# P20_Relay_Board_V1.net
KiCad netlist of a schematic drawn in EAGLE
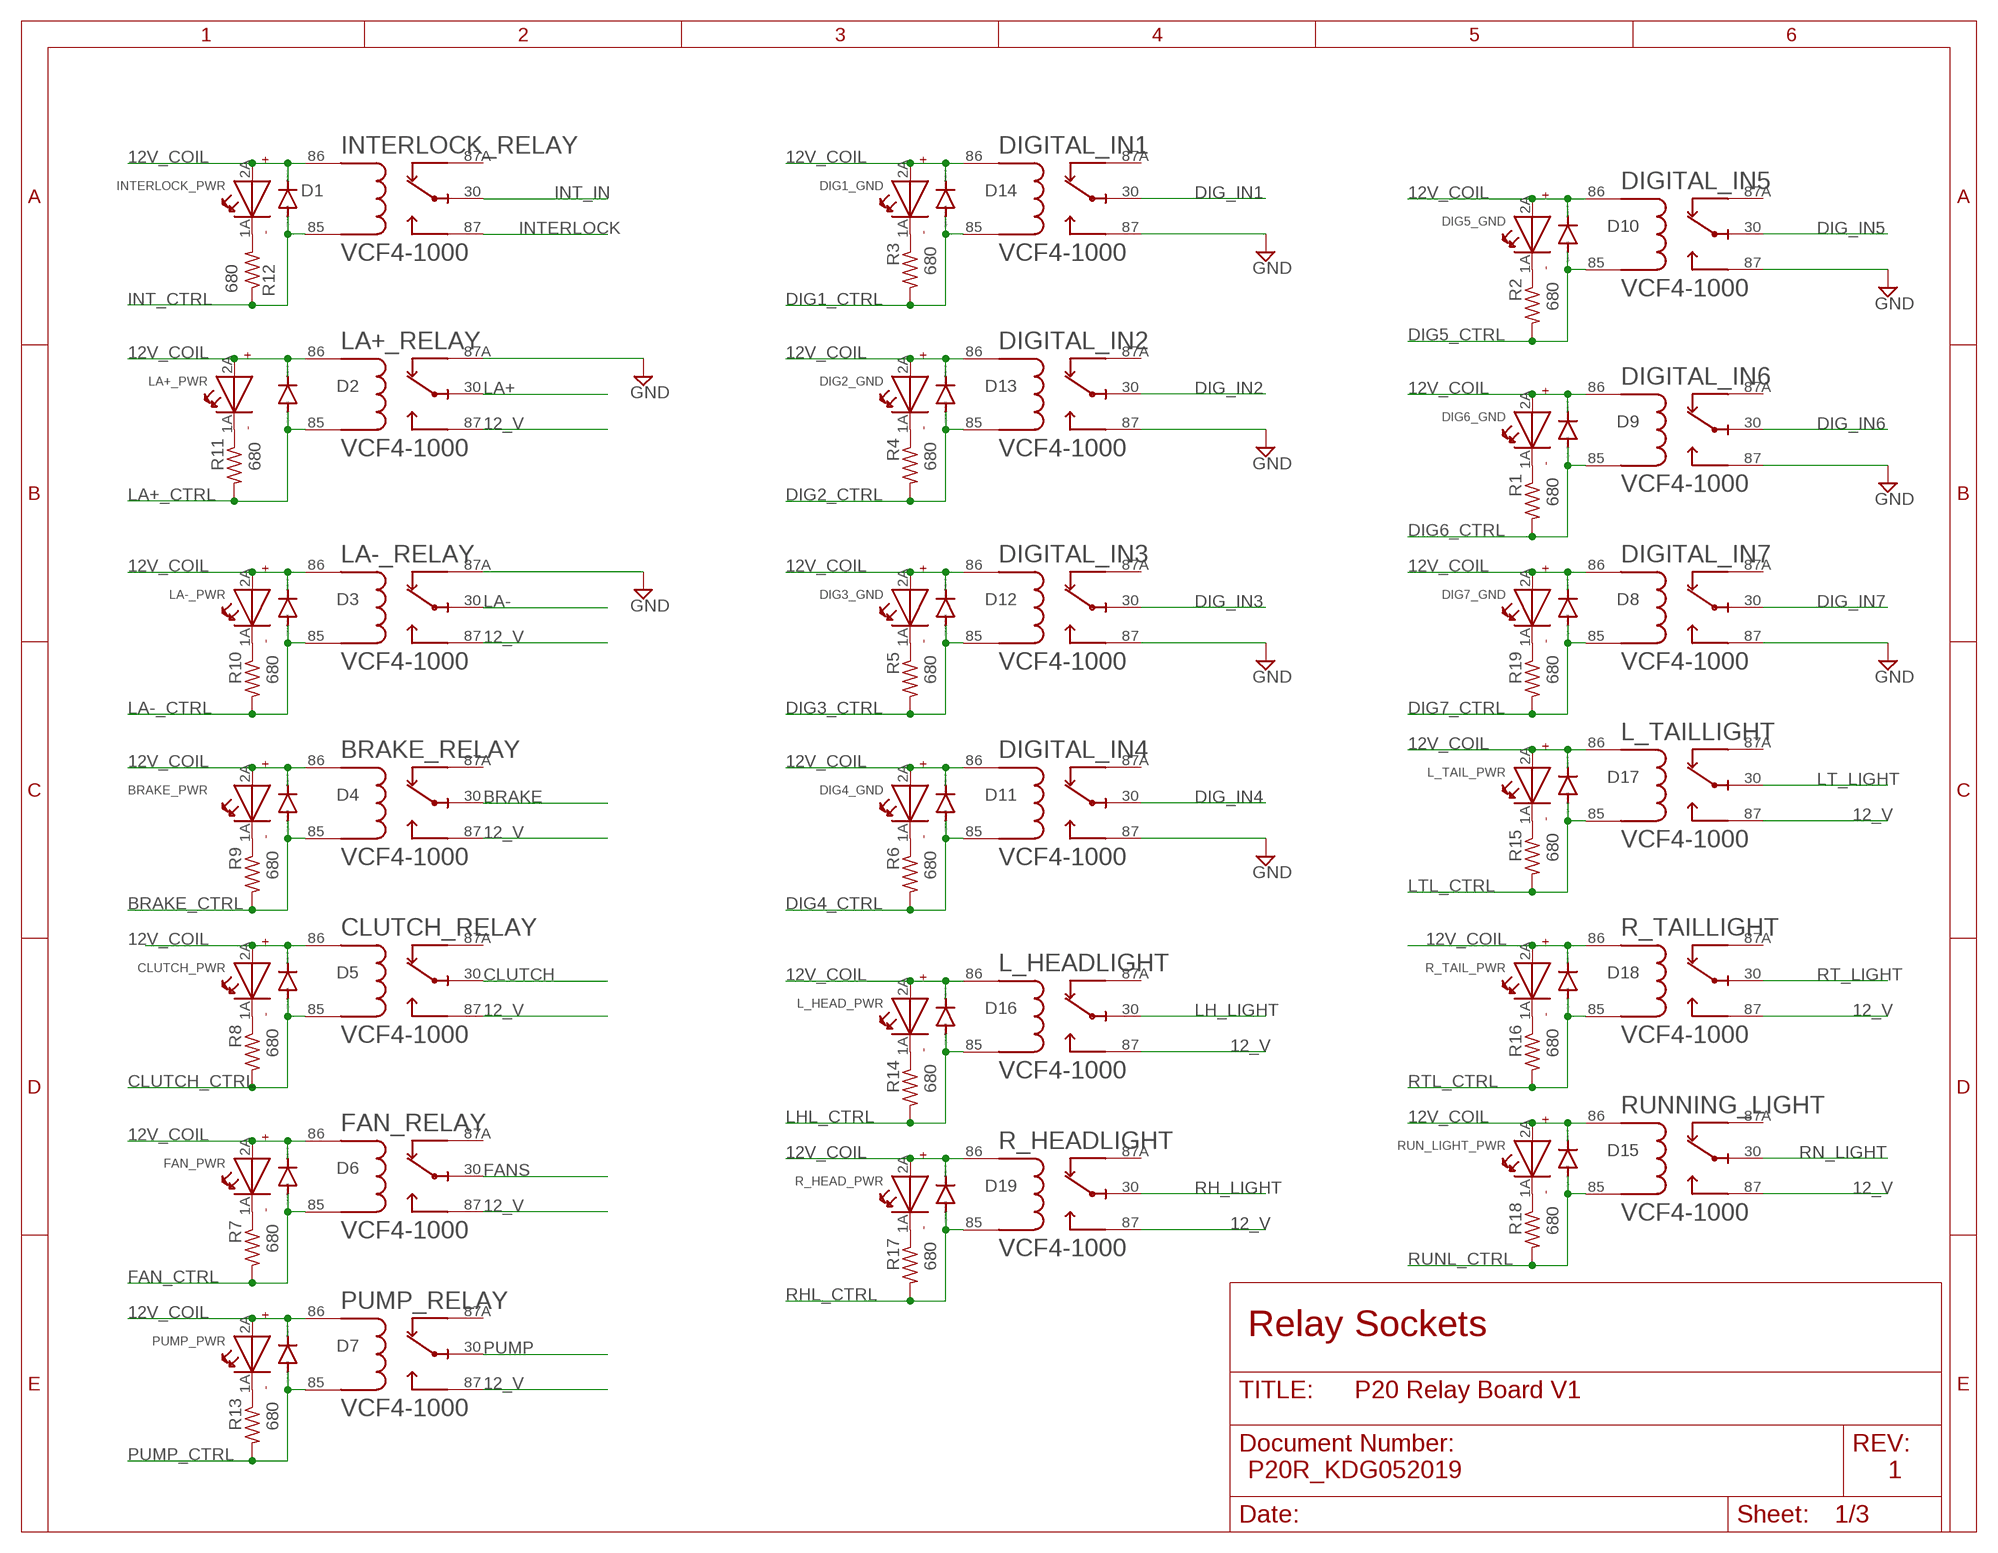
[diagram p0: schematic, sheet 1]
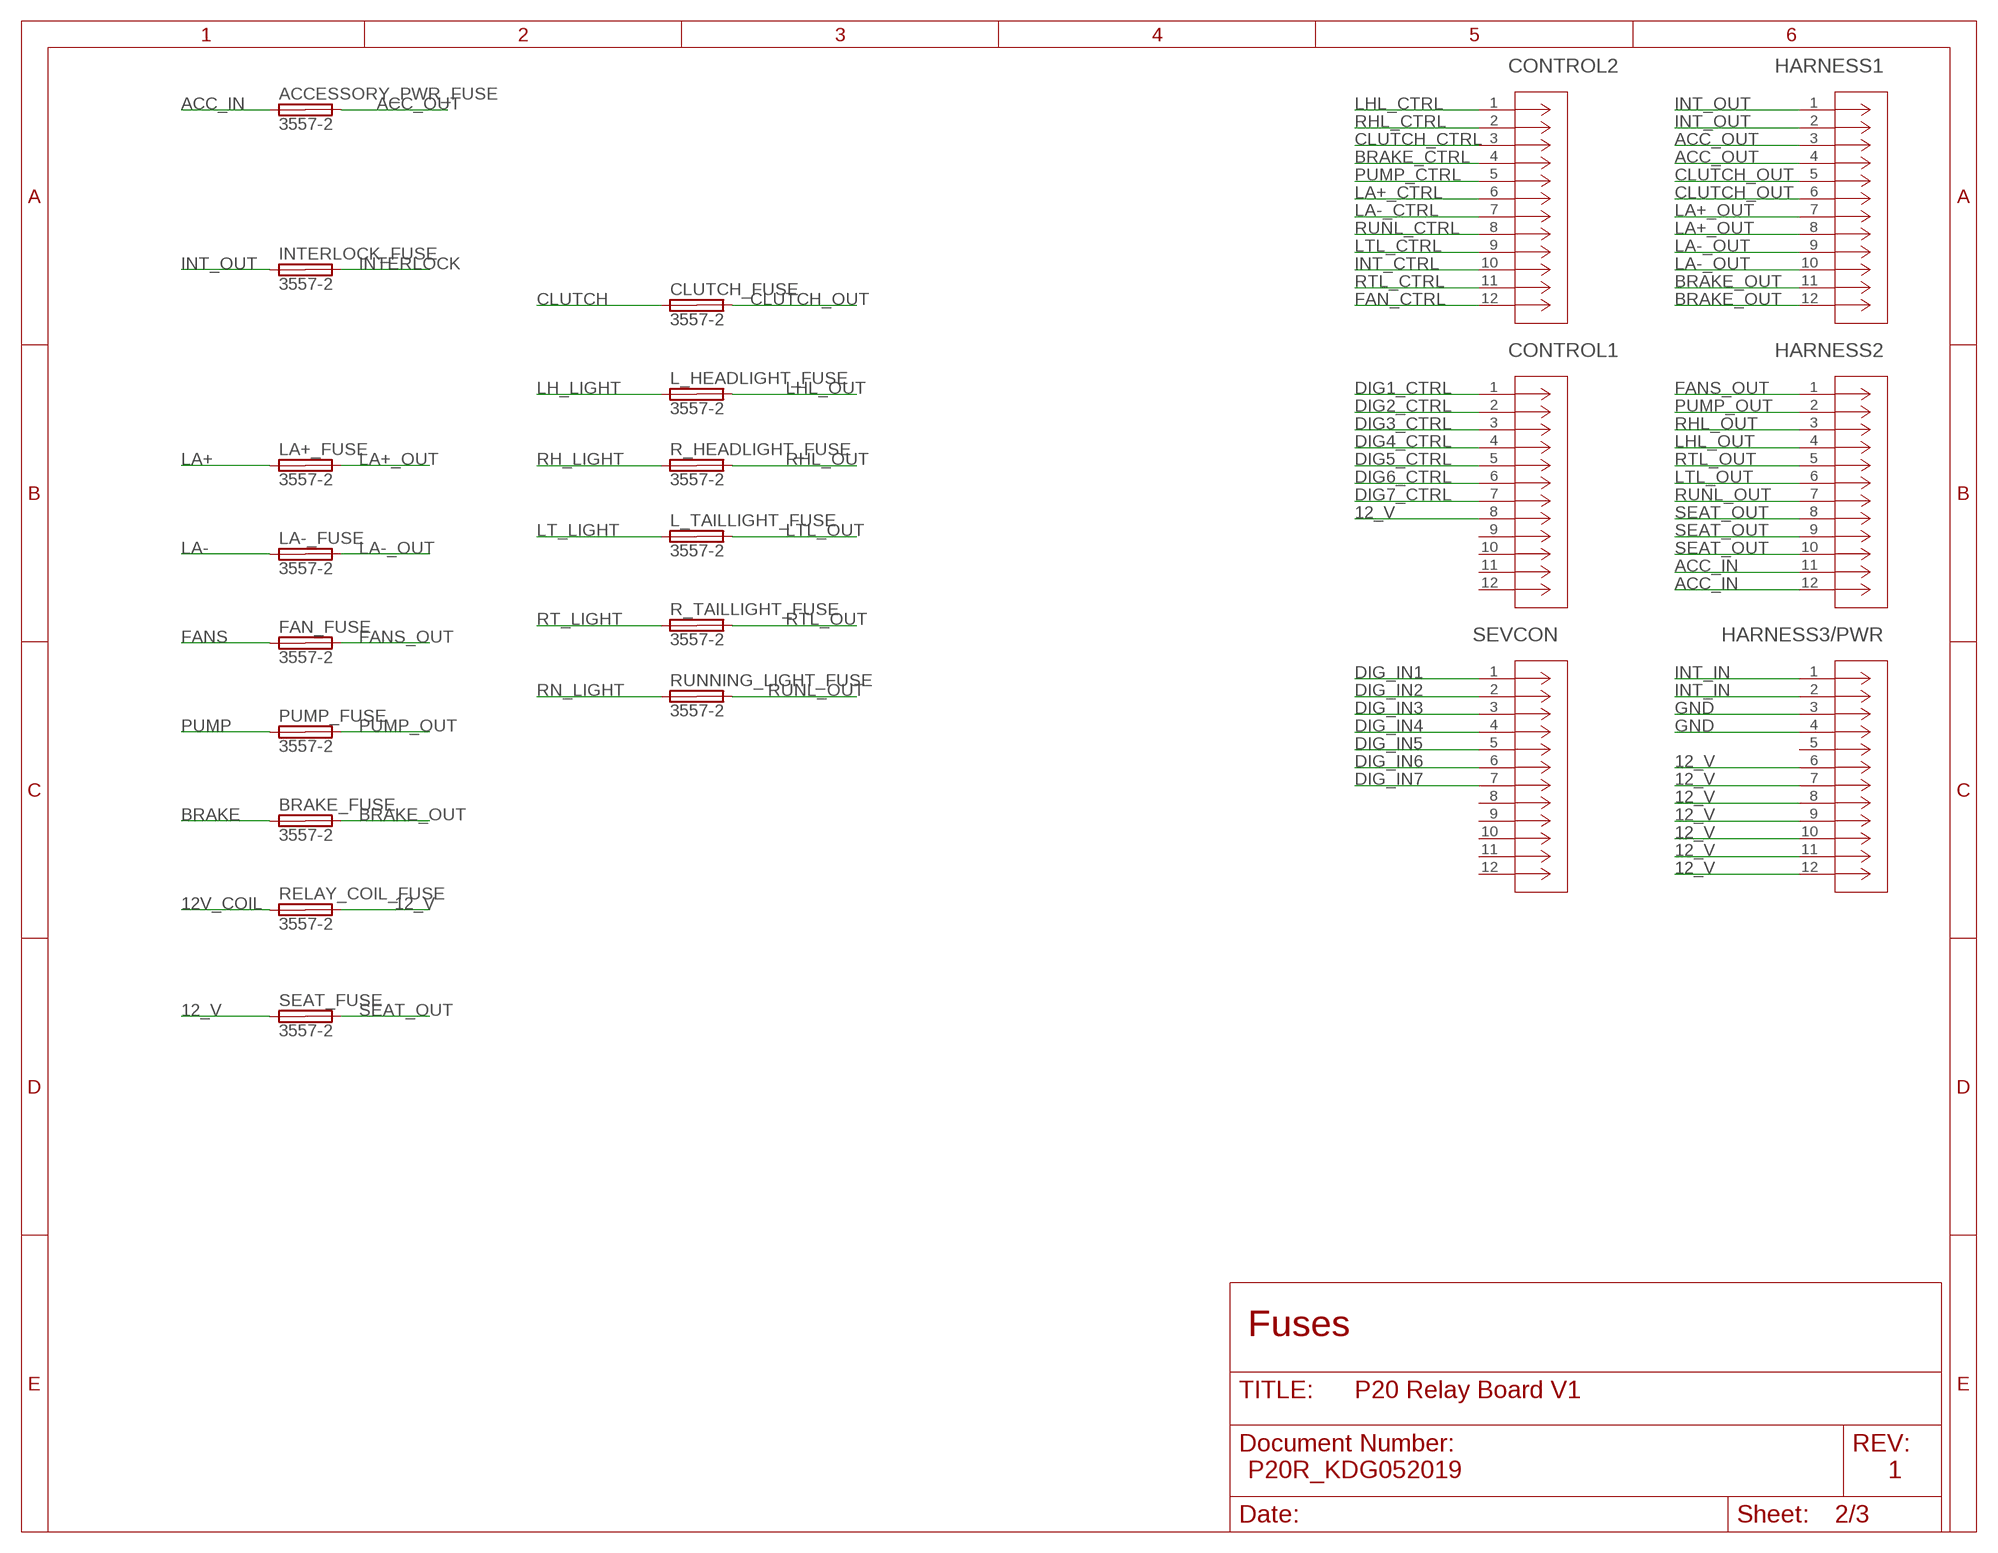
[diagram p1: schematic, sheet 2]
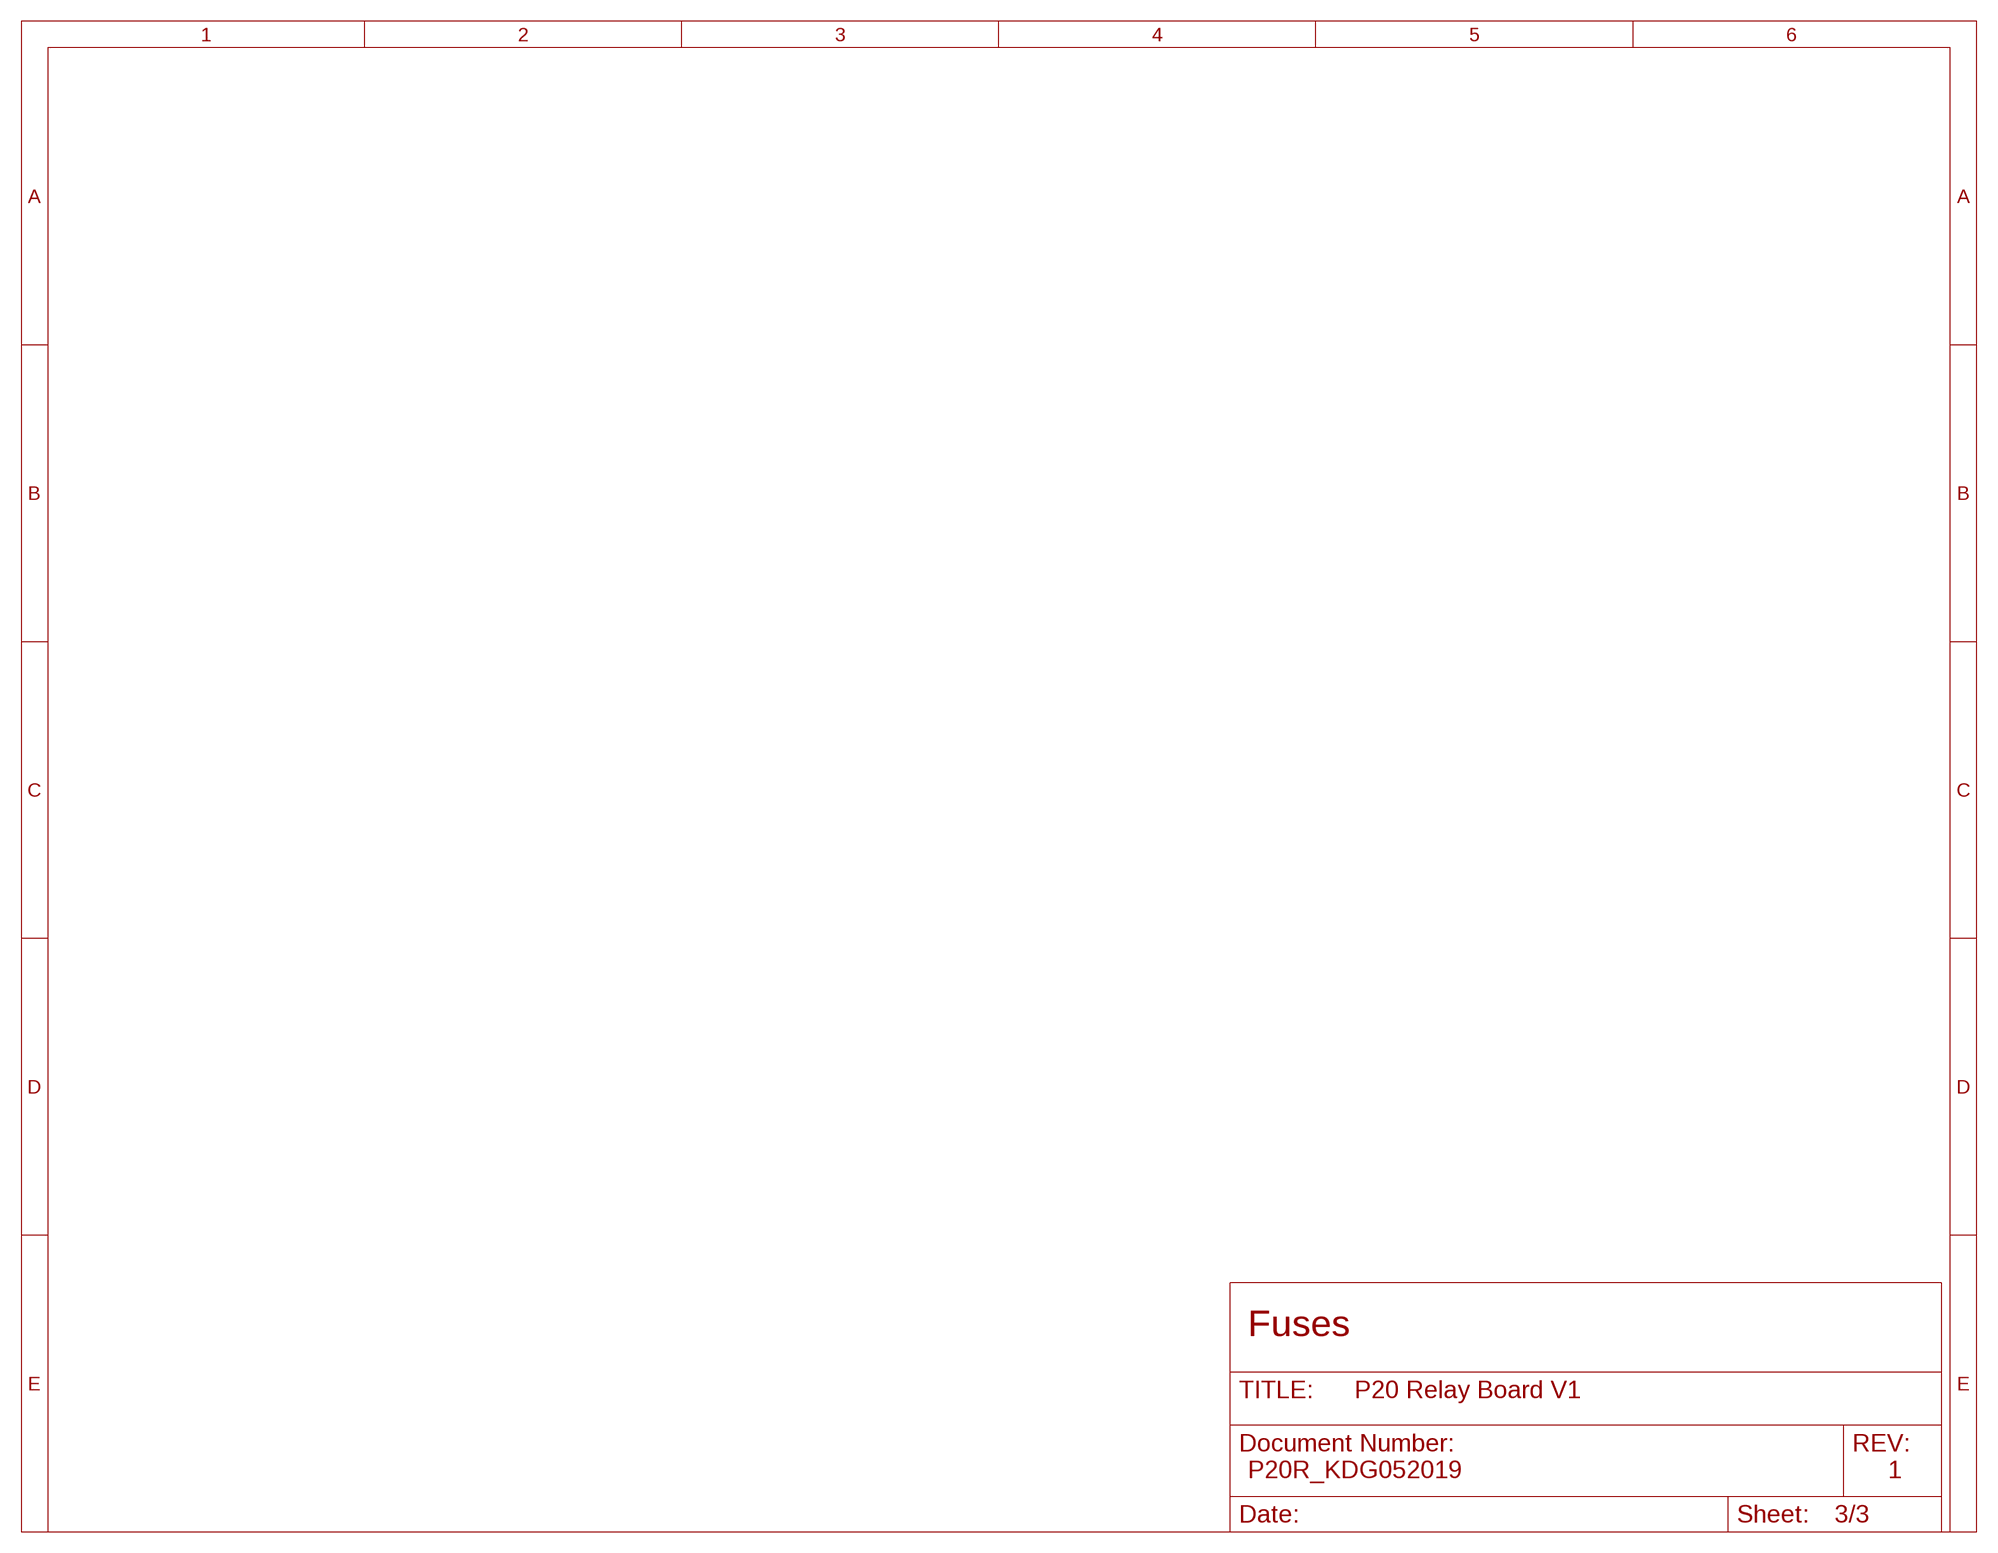
[diagram p2: schematic, sheet 3]

(export (version "E")
  (design (tool "Eeschema 10.0.6"))
  (components
    (comp (ref "ACCESSORY_PWR_FUSE")
      (value "3557-2")
      (footprint "eagle-import:FUSE_3557-2")
      (fields (field (name "MF") "Keystone"))
      (libsource (lib "eagle-import") (part "3557-2"))
    )
    (comp (ref "BRAKE_FUSE")
      (value "3557-2")
      (footprint "eagle-import:FUSE_3557-2")
      (fields (field (name "MF") "Keystone"))
      (libsource (lib "eagle-import") (part "3557-2"))
    )
    (comp (ref "CLUTCH_FUSE")
      (value "3557-2")
      (footprint "eagle-import:FUSE_3557-2")
      (fields (field (name "MF") "Keystone"))
      (libsource (lib "eagle-import") (part "3557-2"))
    )
    (comp (ref "CONTROL1")
      (value "DTM13-12PA")
      (footprint "eagle-import:CONN12_DTM13-12PA")
      (fields (field (name "MANUFACTURER_PART_NUMBER") "DTM1312PA"))
      (libsource (lib "eagle-import") (part "DTM13-12PA"))
    )
    (comp (ref "CONTROL2")
      (value "DTM13-12PA")
      (footprint "eagle-import:CONN12_DTM13-12PA")
      (fields (field (name "MANUFACTURER_PART_NUMBER") "DTM1312PA"))
      (libsource (lib "eagle-import") (part "DTM13-12PA"))
    )
    (comp (ref "FAN_FUSE")
      (value "3557-2")
      (footprint "eagle-import:FUSE_3557-2")
      (fields (field (name "MF") "Keystone"))
      (libsource (lib "eagle-import") (part "3557-2"))
    )
    (comp (ref "HARNESS1")
      (value "DTM13-12PA")
      (footprint "eagle-import:CONN12_DTM13-12PA")
      (fields (field (name "MANUFACTURER_PART_NUMBER") "DTM1312PA"))
      (libsource (lib "eagle-import") (part "DTM13-12PA"))
    )
    (comp (ref "HARNESS2")
      (value "DTM13-12PA")
      (footprint "eagle-import:CONN12_DTM13-12PA")
      (fields (field (name "MANUFACTURER_PART_NUMBER") "DTM1312PA"))
      (libsource (lib "eagle-import") (part "DTM13-12PA"))
    )
    (comp (ref "HARNESS3/PWR")
      (value "DTM13-12PA")
      (footprint "eagle-import:CONN12_DTM13-12PA")
      (fields (field (name "MANUFACTURER_PART_NUMBER") "DTM1312PA"))
      (libsource (lib "eagle-import") (part "DTM13-12PA"))
    )
    (comp (ref "INTERLOCK_FUSE")
      (value "3557-2")
      (footprint "eagle-import:FUSE_3557-2")
      (fields (field (name "MF") "Keystone"))
      (libsource (lib "eagle-import") (part "3557-2"))
    )
    (comp (ref "LA+_FUSE")
      (value "3557-2")
      (footprint "eagle-import:FUSE_3557-2")
      (fields (field (name "MF") "Keystone"))
      (libsource (lib "eagle-import") (part "3557-2"))
    )
    (comp (ref "LA-_FUSE")
      (value "3557-2")
      (footprint "eagle-import:FUSE_3557-2")
      (fields (field (name "MF") "Keystone"))
      (libsource (lib "eagle-import") (part "3557-2"))
    )
    (comp (ref "L_HEADLIGHT_FUSE")
      (value "3557-2")
      (footprint "eagle-import:FUSE_3557-2")
      (fields (field (name "MF") "Keystone"))
      (libsource (lib "eagle-import") (part "3557-2"))
    )
    (comp (ref "L_TAILLIGHT_FUSE")
      (value "3557-2")
      (footprint "eagle-import:FUSE_3557-2")
      (fields (field (name "MF") "Keystone"))
      (libsource (lib "eagle-import") (part "3557-2"))
    )
    (comp (ref "PUMP_FUSE")
      (value "3557-2")
      (footprint "eagle-import:FUSE_3557-2")
      (fields (field (name "MF") "Keystone"))
      (libsource (lib "eagle-import") (part "3557-2"))
    )
    (comp (ref "RELAY_COIL_FUSE")
      (value "3557-2")
      (footprint "eagle-import:FUSE_3557-2")
      (fields (field (name "MF") "Keystone"))
      (libsource (lib "eagle-import") (part "3557-2"))
    )
    (comp (ref "RUNNING_LIGHT_FUSE")
      (value "3557-2")
      (footprint "eagle-import:FUSE_3557-2")
      (fields (field (name "MF") "Keystone"))
      (libsource (lib "eagle-import") (part "3557-2"))
    )
    (comp (ref "R_HEADLIGHT_FUSE")
      (value "3557-2")
      (footprint "eagle-import:FUSE_3557-2")
      (fields (field (name "MF") "Keystone"))
      (libsource (lib "eagle-import") (part "3557-2"))
    )
    (comp (ref "R_TAILLIGHT_FUSE")
      (value "3557-2")
      (footprint "eagle-import:FUSE_3557-2")
      (fields (field (name "MF") "Keystone"))
      (libsource (lib "eagle-import") (part "3557-2"))
    )
    (comp (ref "SEAT_FUSE")
      (value "3557-2")
      (footprint "eagle-import:FUSE_3557-2")
      (fields (field (name "MF") "Keystone"))
      (libsource (lib "eagle-import") (part "3557-2"))
    )
    (comp (ref "SEVCON")
      (value "DTM13-12PA")
      (footprint "eagle-import:CONN12_DTM13-12PA")
      (fields (field (name "MANUFACTURER_PART_NUMBER") "DTM1312PA"))
      (libsource (lib "eagle-import") (part "DTM13-12PA"))
    )
    (comp (ref "BRAKE_PWR")
      (value "WL-TMRW151033BS03000-B")
      (footprint "eagle-import:LED-3MM-ROUND")
      (fields
        (field (name "DIGI-KEY_PART_NUMBER") "732-5013-ND")
        (field (name "MF") "Wurth Electronics")
        (field (name "MP") "151033RS03000")
      )
      (libsource (lib "eagle-import") (part "WL-TMRW151033BS03000-B"))
    )
    (comp (ref "BRAKE_RELAY")
      (value "VCF4-1000")
      (footprint "eagle-import:TE_VCF4-1000")
      (fields
        (field (name "COMMENT") "1393310-3")
        (field (name "DIGI-KEY_PART_NUMBER") "PB232-ND")
        (field (name "MF") "TE Connectivity")
      )
      (libsource (lib "eagle-import") (part "VCF4-1000"))
    )
    (comp (ref "CLUTCH_PWR")
      (value "WL-TMRW151033BS03000-B")
      (footprint "eagle-import:LED-3MM-ROUND")
      (fields
        (field (name "DIGI-KEY_PART_NUMBER") "732-5013-ND")
        (field (name "MF") "Wurth Electronics")
        (field (name "MP") "151033RS03000")
      )
      (libsource (lib "eagle-import") (part "WL-TMRW151033BS03000-B"))
    )
    (comp (ref "CLUTCH_RELAY")
      (value "VCF4-1000")
      (footprint "eagle-import:TE_VCF4-1000")
      (fields
        (field (name "COMMENT") "1393310-3")
        (field (name "DIGI-KEY_PART_NUMBER") "PB232-ND")
        (field (name "MF") "TE Connectivity")
      )
      (libsource (lib "eagle-import") (part "VCF4-1000"))
    )
    (comp (ref "D1")
      (value "1N4004")
      (footprint "eagle-import:DO41-10")
      (libsource (lib "eagle-import") (part "1N4004"))
    )
    (comp (ref "D2")
      (value "1N4004")
      (footprint "eagle-import:DO41-10")
      (libsource (lib "eagle-import") (part "1N4004"))
    )
    (comp (ref "D3")
      (value "1N4004")
      (footprint "eagle-import:DO41-10")
      (libsource (lib "eagle-import") (part "1N4004"))
    )
    (comp (ref "D4")
      (value "1N4004")
      (footprint "eagle-import:DO41-10")
      (libsource (lib "eagle-import") (part "1N4004"))
    )
    (comp (ref "D5")
      (value "1N4004")
      (footprint "eagle-import:DO41-10")
      (libsource (lib "eagle-import") (part "1N4004"))
    )
    (comp (ref "D6")
      (value "1N4004")
      (footprint "eagle-import:DO41-10")
      (libsource (lib "eagle-import") (part "1N4004"))
    )
    (comp (ref "D7")
      (value "1N4004")
      (footprint "eagle-import:DO41-10")
      (libsource (lib "eagle-import") (part "1N4004"))
    )
    (comp (ref "D8")
      (value "1N4004")
      (footprint "eagle-import:DO41-10")
      (libsource (lib "eagle-import") (part "1N4004"))
    )
    (comp (ref "D9")
      (value "1N4004")
      (footprint "eagle-import:DO41-10")
      (libsource (lib "eagle-import") (part "1N4004"))
    )
    (comp (ref "D10")
      (value "1N4004")
      (footprint "eagle-import:DO41-10")
      (libsource (lib "eagle-import") (part "1N4004"))
    )
    (comp (ref "D11")
      (value "1N4004")
      (footprint "eagle-import:DO41-10")
      (libsource (lib "eagle-import") (part "1N4004"))
    )
    (comp (ref "D12")
      (value "1N4004")
      (footprint "eagle-import:DO41-10")
      (libsource (lib "eagle-import") (part "1N4004"))
    )
    (comp (ref "D13")
      (value "1N4004")
      (footprint "eagle-import:DO41-10")
      (libsource (lib "eagle-import") (part "1N4004"))
    )
    (comp (ref "D14")
      (value "1N4004")
      (footprint "eagle-import:DO41-10")
      (libsource (lib "eagle-import") (part "1N4004"))
    )
    (comp (ref "D15")
      (value "1N4004")
      (footprint "eagle-import:DO41-10")
      (libsource (lib "eagle-import") (part "1N4004"))
    )
    (comp (ref "D16")
      (value "1N4004")
      (footprint "eagle-import:DO41-10")
      (libsource (lib "eagle-import") (part "1N4004"))
    )
    (comp (ref "D17")
      (value "1N4004")
      (footprint "eagle-import:DO41-10")
      (libsource (lib "eagle-import") (part "1N4004"))
    )
    (comp (ref "D18")
      (value "1N4004")
      (footprint "eagle-import:DO41-10")
      (libsource (lib "eagle-import") (part "1N4004"))
    )
    (comp (ref "D19")
      (value "1N4004")
      (footprint "eagle-import:DO41-10")
      (libsource (lib "eagle-import") (part "1N4004"))
    )
    (comp (ref "DIG1_GND")
      (value "WL-TMRW151033BS03000-B")
      (footprint "eagle-import:LED-3MM-ROUND")
      (fields
        (field (name "DIGI-KEY_PART_NUMBER") "732-5013-ND")
        (field (name "MF") "Wurth Electronics")
        (field (name "MP") "151033RS03000")
      )
      (libsource (lib "eagle-import") (part "WL-TMRW151033BS03000-B"))
    )
    (comp (ref "DIG2_GND")
      (value "WL-TMRW151033BS03000-B")
      (footprint "eagle-import:LED-3MM-ROUND")
      (fields
        (field (name "DIGI-KEY_PART_NUMBER") "732-5013-ND")
        (field (name "MF") "Wurth Electronics")
        (field (name "MP") "151033RS03000")
      )
      (libsource (lib "eagle-import") (part "WL-TMRW151033BS03000-B"))
    )
    (comp (ref "DIG3_GND")
      (value "WL-TMRW151033BS03000-B")
      (footprint "eagle-import:LED-3MM-ROUND")
      (fields
        (field (name "DIGI-KEY_PART_NUMBER") "732-5013-ND")
        (field (name "MF") "Wurth Electronics")
        (field (name "MP") "151033RS03000")
      )
      (libsource (lib "eagle-import") (part "WL-TMRW151033BS03000-B"))
    )
    (comp (ref "DIG4_GND")
      (value "WL-TMRW151033BS03000-B")
      (footprint "eagle-import:LED-3MM-ROUND")
      (fields
        (field (name "DIGI-KEY_PART_NUMBER") "732-5013-ND")
        (field (name "MF") "Wurth Electronics")
        (field (name "MP") "151033RS03000")
      )
      (libsource (lib "eagle-import") (part "WL-TMRW151033BS03000-B"))
    )
    (comp (ref "DIG5_GND")
      (value "WL-TMRW151033BS03000-B")
      (footprint "eagle-import:LED-3MM-ROUND")
      (fields
        (field (name "DIGI-KEY_PART_NUMBER") "732-5013-ND")
        (field (name "MF") "Wurth Electronics")
        (field (name "MP") "151033RS03000")
      )
      (libsource (lib "eagle-import") (part "WL-TMRW151033BS03000-B"))
    )
    (comp (ref "DIG6_GND")
      (value "WL-TMRW151033BS03000-B")
      (footprint "eagle-import:LED-3MM-ROUND")
      (fields
        (field (name "DIGI-KEY_PART_NUMBER") "732-5013-ND")
        (field (name "MF") "Wurth Electronics")
        (field (name "MP") "151033RS03000")
      )
      (libsource (lib "eagle-import") (part "WL-TMRW151033BS03000-B"))
    )
    (comp (ref "DIG7_GND")
      (value "WL-TMRW151033BS03000-B")
      (footprint "eagle-import:LED-3MM-ROUND")
      (fields
        (field (name "DIGI-KEY_PART_NUMBER") "732-5013-ND")
        (field (name "MF") "Wurth Electronics")
        (field (name "MP") "151033RS03000")
      )
      (libsource (lib "eagle-import") (part "WL-TMRW151033BS03000-B"))
    )
    (comp (ref "DIGITAL_IN1")
      (value "VCF4-1000")
      (footprint "eagle-import:TE_VCF4-1000")
      (fields
        (field (name "COMMENT") "1393310-3")
        (field (name "DIGI-KEY_PART_NUMBER") "PB232-ND")
        (field (name "MF") "TE Connectivity")
      )
      (libsource (lib "eagle-import") (part "VCF4-1000"))
    )
    (comp (ref "DIGITAL_IN2")
      (value "VCF4-1000")
      (footprint "eagle-import:TE_VCF4-1000")
      (fields
        (field (name "COMMENT") "1393310-3")
        (field (name "DIGI-KEY_PART_NUMBER") "PB232-ND")
        (field (name "MF") "TE Connectivity")
      )
      (libsource (lib "eagle-import") (part "VCF4-1000"))
    )
    (comp (ref "DIGITAL_IN3")
      (value "VCF4-1000")
      (footprint "eagle-import:TE_VCF4-1000")
      (fields
        (field (name "COMMENT") "1393310-3")
        (field (name "DIGI-KEY_PART_NUMBER") "PB232-ND")
        (field (name "MF") "TE Connectivity")
      )
      (libsource (lib "eagle-import") (part "VCF4-1000"))
    )
    (comp (ref "DIGITAL_IN4")
      (value "VCF4-1000")
      (footprint "eagle-import:TE_VCF4-1000")
      (fields
        (field (name "COMMENT") "1393310-3")
        (field (name "DIGI-KEY_PART_NUMBER") "PB232-ND")
        (field (name "MF") "TE Connectivity")
      )
      (libsource (lib "eagle-import") (part "VCF4-1000"))
    )
    (comp (ref "DIGITAL_IN5")
      (value "VCF4-1000")
      (footprint "eagle-import:TE_VCF4-1000")
      (fields
        (field (name "COMMENT") "1393310-3")
        (field (name "DIGI-KEY_PART_NUMBER") "PB232-ND")
        (field (name "MF") "TE Connectivity")
      )
      (libsource (lib "eagle-import") (part "VCF4-1000"))
    )
    (comp (ref "DIGITAL_IN6")
      (value "VCF4-1000")
      (footprint "eagle-import:TE_VCF4-1000")
      (fields
        (field (name "COMMENT") "1393310-3")
        (field (name "DIGI-KEY_PART_NUMBER") "PB232-ND")
        (field (name "MF") "TE Connectivity")
      )
      (libsource (lib "eagle-import") (part "VCF4-1000"))
    )
    (comp (ref "DIGITAL_IN7")
      (value "VCF4-1000")
      (footprint "eagle-import:TE_VCF4-1000")
      (fields
        (field (name "COMMENT") "1393310-3")
        (field (name "DIGI-KEY_PART_NUMBER") "PB232-ND")
        (field (name "MF") "TE Connectivity")
      )
      (libsource (lib "eagle-import") (part "VCF4-1000"))
    )
    (comp (ref "FAN_PWR")
      (value "WL-TMRW151033BS03000-B")
      (footprint "eagle-import:LED-3MM-ROUND")
      (fields
        (field (name "DIGI-KEY_PART_NUMBER") "732-5013-ND")
        (field (name "MF") "Wurth Electronics")
        (field (name "MP") "151033RS03000")
      )
      (libsource (lib "eagle-import") (part "WL-TMRW151033BS03000-B"))
    )
    (comp (ref "FAN_RELAY")
      (value "VCF4-1000")
      (footprint "eagle-import:TE_VCF4-1000")
      (fields
        (field (name "COMMENT") "1393310-3")
        (field (name "DIGI-KEY_PART_NUMBER") "PB232-ND")
        (field (name "MF") "TE Connectivity")
      )
      (libsource (lib "eagle-import") (part "VCF4-1000"))
    )
    (comp (ref "INTERLOCK_PWR")
      (value "WL-TMRW151033BS03000-B")
      (footprint "eagle-import:LED-3MM-ROUND")
      (fields
        (field (name "DIGI-KEY_PART_NUMBER") "732-5013-ND")
        (field (name "MF") "Wurth Electronics")
        (field (name "MP") "151033RS03000")
      )
      (libsource (lib "eagle-import") (part "WL-TMRW151033BS03000-B"))
    )
    (comp (ref "INTERLOCK_RELAY")
      (value "VCF4-1000")
      (footprint "eagle-import:TE_VCF4-1000")
      (fields
        (field (name "COMMENT") "1393310-3")
        (field (name "DIGI-KEY_PART_NUMBER") "PB232-ND")
        (field (name "MF") "TE Connectivity")
      )
      (libsource (lib "eagle-import") (part "VCF4-1000"))
    )
    (comp (ref "LA+_PWR")
      (value "WL-TMRW151033BS03000-B")
      (footprint "eagle-import:LED-3MM-ROUND")
      (fields
        (field (name "DIGI-KEY_PART_NUMBER") "732-5013-ND")
        (field (name "MF") "Wurth Electronics")
        (field (name "MP") "151033RS03000")
      )
      (libsource (lib "eagle-import") (part "WL-TMRW151033BS03000-B"))
    )
    (comp (ref "LA+_RELAY")
      (value "VCF4-1000")
      (footprint "eagle-import:TE_VCF4-1000")
      (fields
        (field (name "COMMENT") "1393310-3")
        (field (name "DIGI-KEY_PART_NUMBER") "PB232-ND")
        (field (name "MF") "TE Connectivity")
      )
      (libsource (lib "eagle-import") (part "VCF4-1000"))
    )
    (comp (ref "LA-_PWR")
      (value "WL-TMRW151033BS03000-B")
      (footprint "eagle-import:LED-3MM-ROUND")
      (fields
        (field (name "DIGI-KEY_PART_NUMBER") "732-5013-ND")
        (field (name "MF") "Wurth Electronics")
        (field (name "MP") "151033RS03000")
      )
      (libsource (lib "eagle-import") (part "WL-TMRW151033BS03000-B"))
    )
    (comp (ref "LA-_RELAY")
      (value "VCF4-1000")
      (footprint "eagle-import:TE_VCF4-1000")
      (fields
        (field (name "COMMENT") "1393310-3")
        (field (name "DIGI-KEY_PART_NUMBER") "PB232-ND")
        (field (name "MF") "TE Connectivity")
      )
      (libsource (lib "eagle-import") (part "VCF4-1000"))
    )
    (comp (ref "L_HEADLIGHT")
      (value "VCF4-1000")
      (footprint "eagle-import:TE_VCF4-1000")
      (fields
        (field (name "COMMENT") "1393310-3")
        (field (name "DIGI-KEY_PART_NUMBER") "PB232-ND")
        (field (name "MF") "TE Connectivity")
      )
      (libsource (lib "eagle-import") (part "VCF4-1000"))
    )
    (comp (ref "L_HEAD_PWR")
      (value "WL-TMRW151033BS03000-B")
      (footprint "eagle-import:LED-3MM-ROUND")
      (fields
        (field (name "DIGI-KEY_PART_NUMBER") "732-5013-ND")
        (field (name "MF") "Wurth Electronics")
        (field (name "MP") "151033RS03000")
      )
      (libsource (lib "eagle-import") (part "WL-TMRW151033BS03000-B"))
    )
    (comp (ref "L_TAILLIGHT")
      (value "VCF4-1000")
      (footprint "eagle-import:TE_VCF4-1000")
      (fields
        (field (name "COMMENT") "1393310-3")
        (field (name "DIGI-KEY_PART_NUMBER") "PB232-ND")
        (field (name "MF") "TE Connectivity")
      )
      (libsource (lib "eagle-import") (part "VCF4-1000"))
    )
    (comp (ref "L_TAIL_PWR")
      (value "WL-TMRW151033BS03000-B")
      (footprint "eagle-import:LED-3MM-ROUND")
      (fields
        (field (name "DIGI-KEY_PART_NUMBER") "732-5013-ND")
        (field (name "MF") "Wurth Electronics")
        (field (name "MP") "151033RS03000")
      )
      (libsource (lib "eagle-import") (part "WL-TMRW151033BS03000-B"))
    )
    (comp (ref "PUMP_PWR")
      (value "WL-TMRW151033BS03000-B")
      (footprint "eagle-import:LED-3MM-ROUND")
      (fields
        (field (name "DIGI-KEY_PART_NUMBER") "732-5013-ND")
        (field (name "MF") "Wurth Electronics")
        (field (name "MP") "151033RS03000")
      )
      (libsource (lib "eagle-import") (part "WL-TMRW151033BS03000-B"))
    )
    (comp (ref "PUMP_RELAY")
      (value "VCF4-1000")
      (footprint "eagle-import:TE_VCF4-1000")
      (fields
        (field (name "COMMENT") "1393310-3")
        (field (name "DIGI-KEY_PART_NUMBER") "PB232-ND")
        (field (name "MF") "TE Connectivity")
      )
      (libsource (lib "eagle-import") (part "VCF4-1000"))
    )
    (comp (ref "R1")
      (value "680")
      (footprint "eagle-import:0207_10")
      (libsource (lib "eagle-import") (part "R-US_0207/10"))
    )
    (comp (ref "R2")
      (value "680")
      (footprint "eagle-import:0207_10")
      (libsource (lib "eagle-import") (part "R-US_0207/10"))
    )
    (comp (ref "R3")
      (value "680")
      (footprint "eagle-import:0207_10")
      (libsource (lib "eagle-import") (part "R-US_0207/10"))
    )
    (comp (ref "R4")
      (value "680")
      (footprint "eagle-import:0207_10")
      (libsource (lib "eagle-import") (part "R-US_0207/10"))
    )
    (comp (ref "R5")
      (value "680")
      (footprint "eagle-import:0207_10")
      (libsource (lib "eagle-import") (part "R-US_0207/10"))
    )
    (comp (ref "R6")
      (value "680")
      (footprint "eagle-import:0207_10")
      (libsource (lib "eagle-import") (part "R-US_0207/10"))
    )
    (comp (ref "R7")
      (value "680")
      (footprint "eagle-import:0207_10")
      (libsource (lib "eagle-import") (part "R-US_0207/10"))
    )
    (comp (ref "R8")
      (value "680")
      (footprint "eagle-import:0207_10")
      (libsource (lib "eagle-import") (part "R-US_0207/10"))
    )
    (comp (ref "R9")
      (value "680")
      (footprint "eagle-import:0207_10")
      (libsource (lib "eagle-import") (part "R-US_0207/10"))
    )
    (comp (ref "R10")
      (value "680")
      (footprint "eagle-import:0207_10")
      (libsource (lib "eagle-import") (part "R-US_0207/10"))
    )
    (comp (ref "R11")
      (value "680")
      (footprint "eagle-import:0207_10")
      (libsource (lib "eagle-import") (part "R-US_0207/10"))
    )
    (comp (ref "R12")
      (value "680")
      (footprint "eagle-import:0207_10")
      (libsource (lib "eagle-import") (part "R-US_0207/10"))
    )
    (comp (ref "R13")
      (value "680")
      (footprint "eagle-import:0207_10")
      (libsource (lib "eagle-import") (part "R-US_0207/10"))
    )
    (comp (ref "R14")
      (value "680")
      (footprint "eagle-import:0207_10")
      (libsource (lib "eagle-import") (part "R-US_0207/10"))
    )
    (comp (ref "R15")
      (value "680")
      (footprint "eagle-import:0207_10")
      (libsource (lib "eagle-import") (part "R-US_0207/10"))
    )
    (comp (ref "R16")
      (value "680")
      (footprint "eagle-import:0207_10")
      (libsource (lib "eagle-import") (part "R-US_0207/10"))
    )
    (comp (ref "R17")
      (value "680")
      (footprint "eagle-import:0207_10")
      (libsource (lib "eagle-import") (part "R-US_0207/10"))
    )
    (comp (ref "R18")
      (value "680")
      (footprint "eagle-import:0207_10")
      (libsource (lib "eagle-import") (part "R-US_0207/10"))
    )
    (comp (ref "R19")
      (value "680")
      (footprint "eagle-import:0207_10")
      (libsource (lib "eagle-import") (part "R-US_0207/10"))
    )
    (comp (ref "RUNNING_LIGHT")
      (value "VCF4-1000")
      (footprint "eagle-import:TE_VCF4-1000")
      (fields
        (field (name "COMMENT") "1393310-3")
        (field (name "DIGI-KEY_PART_NUMBER") "PB232-ND")
        (field (name "MF") "TE Connectivity")
      )
      (libsource (lib "eagle-import") (part "VCF4-1000"))
    )
    (comp (ref "RUN_LIGHT_PWR")
      (value "WL-TMRW151033BS03000-B")
      (footprint "eagle-import:LED-3MM-ROUND")
      (fields
        (field (name "DIGI-KEY_PART_NUMBER") "732-5013-ND")
        (field (name "MF") "Wurth Electronics")
        (field (name "MP") "151033RS03000")
      )
      (libsource (lib "eagle-import") (part "WL-TMRW151033BS03000-B"))
    )
    (comp (ref "R_HEADLIGHT")
      (value "VCF4-1000")
      (footprint "eagle-import:TE_VCF4-1000")
      (fields
        (field (name "COMMENT") "1393310-3")
        (field (name "DIGI-KEY_PART_NUMBER") "PB232-ND")
        (field (name "MF") "TE Connectivity")
      )
      (libsource (lib "eagle-import") (part "VCF4-1000"))
    )
    (comp (ref "R_HEAD_PWR")
      (value "WL-TMRW151033BS03000-B")
      (footprint "eagle-import:LED-3MM-ROUND")
      (fields
        (field (name "DIGI-KEY_PART_NUMBER") "732-5013-ND")
        (field (name "MF") "Wurth Electronics")
        (field (name "MP") "151033RS03000")
      )
      (libsource (lib "eagle-import") (part "WL-TMRW151033BS03000-B"))
    )
    (comp (ref "R_TAILLIGHT")
      (value "VCF4-1000")
      (footprint "eagle-import:TE_VCF4-1000")
      (fields
        (field (name "COMMENT") "1393310-3")
        (field (name "DIGI-KEY_PART_NUMBER") "PB232-ND")
        (field (name "MF") "TE Connectivity")
      )
      (libsource (lib "eagle-import") (part "VCF4-1000"))
    )
    (comp (ref "R_TAIL_PWR")
      (value "WL-TMRW151033BS03000-B")
      (footprint "eagle-import:LED-3MM-ROUND")
      (fields
        (field (name "DIGI-KEY_PART_NUMBER") "732-5013-ND")
        (field (name "MF") "Wurth Electronics")
        (field (name "MP") "151033RS03000")
      )
      (libsource (lib "eagle-import") (part "WL-TMRW151033BS03000-B"))
    )
  )
  (nets
    (net (code "1") (name "12V_COIL") (class "Default")
      (node (ref "BRAKE_PWR") (pin "2A") (pinfunction "+_2A") (pintype "bidirectional"))
      (node (ref "BRAKE_RELAY") (pin "86") (pinfunction "86_86") (pintype "passive"))
      (node (ref "CLUTCH_PWR") (pin "2A") (pinfunction "+_2A") (pintype "bidirectional"))
      (node (ref "CLUTCH_RELAY") (pin "86") (pinfunction "86_86") (pintype "passive"))
      (node (ref "D1") (pin "C") (pinfunction "C_C") (pintype "passive"))
      (node (ref "D10") (pin "C") (pinfunction "C_C") (pintype "passive"))
      (node (ref "D11") (pin "C") (pinfunction "C_C") (pintype "passive"))
      (node (ref "D12") (pin "C") (pinfunction "C_C") (pintype "passive"))
      (node (ref "D13") (pin "C") (pinfunction "C_C") (pintype "passive"))
      (node (ref "D14") (pin "C") (pinfunction "C_C") (pintype "passive"))
      (node (ref "D15") (pin "C") (pinfunction "C_C") (pintype "passive"))
      (node (ref "D16") (pin "C") (pinfunction "C_C") (pintype "passive"))
      (node (ref "D17") (pin "C") (pinfunction "C_C") (pintype "passive"))
      (node (ref "D18") (pin "C") (pinfunction "C_C") (pintype "passive"))
      (node (ref "D19") (pin "C") (pinfunction "C_C") (pintype "passive"))
      (node (ref "D2") (pin "C") (pinfunction "C_C") (pintype "passive"))
      (node (ref "D3") (pin "C") (pinfunction "C_C") (pintype "passive"))
      (node (ref "D4") (pin "C") (pinfunction "C_C") (pintype "passive"))
      (node (ref "D5") (pin "C") (pinfunction "C_C") (pintype "passive"))
      (node (ref "D6") (pin "C") (pinfunction "C_C") (pintype "passive"))
      (node (ref "D7") (pin "C") (pinfunction "C_C") (pintype "passive"))
      (node (ref "D8") (pin "C") (pinfunction "C_C") (pintype "passive"))
      (node (ref "D9") (pin "C") (pinfunction "C_C") (pintype "passive"))
      (node (ref "DIG1_GND") (pin "2A") (pinfunction "+_2A") (pintype "bidirectional"))
      (node (ref "DIG2_GND") (pin "2A") (pinfunction "+_2A") (pintype "bidirectional"))
      (node (ref "DIG3_GND") (pin "2A") (pinfunction "+_2A") (pintype "bidirectional"))
      (node (ref "DIG4_GND") (pin "2A") (pinfunction "+_2A") (pintype "bidirectional"))
      (node (ref "DIG5_GND") (pin "2A") (pinfunction "+_2A") (pintype "bidirectional"))
      (node (ref "DIG6_GND") (pin "2A") (pinfunction "+_2A") (pintype "bidirectional"))
      (node (ref "DIG7_GND") (pin "2A") (pinfunction "+_2A") (pintype "bidirectional"))
      (node (ref "DIGITAL_IN1") (pin "86") (pinfunction "86_86") (pintype "passive"))
      (node (ref "DIGITAL_IN2") (pin "86") (pinfunction "86_86") (pintype "passive"))
      (node (ref "DIGITAL_IN3") (pin "86") (pinfunction "86_86") (pintype "passive"))
      (node (ref "DIGITAL_IN4") (pin "86") (pinfunction "86_86") (pintype "passive"))
      (node (ref "DIGITAL_IN5") (pin "86") (pinfunction "86_86") (pintype "passive"))
      (node (ref "DIGITAL_IN6") (pin "86") (pinfunction "86_86") (pintype "passive"))
      (node (ref "DIGITAL_IN7") (pin "86") (pinfunction "86_86") (pintype "passive"))
      (node (ref "FAN_PWR") (pin "2A") (pinfunction "+_2A") (pintype "bidirectional"))
      (node (ref "FAN_RELAY") (pin "86") (pinfunction "86_86") (pintype "passive"))
      (node (ref "INTERLOCK_PWR") (pin "2A") (pinfunction "+_2A") (pintype "bidirectional"))
      (node (ref "INTERLOCK_RELAY") (pin "86") (pinfunction "86_86") (pintype "passive"))
      (node (ref "LA+_PWR") (pin "2A") (pinfunction "+_2A") (pintype "bidirectional"))
      (node (ref "LA+_RELAY") (pin "86") (pinfunction "86_86") (pintype "passive"))
      (node (ref "LA-_PWR") (pin "2A") (pinfunction "+_2A") (pintype "bidirectional"))
      (node (ref "LA-_RELAY") (pin "86") (pinfunction "86_86") (pintype "passive"))
      (node (ref "L_HEADLIGHT") (pin "86") (pinfunction "86_86") (pintype "passive"))
      (node (ref "L_HEAD_PWR") (pin "2A") (pinfunction "+_2A") (pintype "bidirectional"))
      (node (ref "L_TAILLIGHT") (pin "86") (pinfunction "86_86") (pintype "passive"))
      (node (ref "L_TAIL_PWR") (pin "2A") (pinfunction "+_2A") (pintype "bidirectional"))
      (node (ref "PUMP_PWR") (pin "2A") (pinfunction "+_2A") (pintype "bidirectional"))
      (node (ref "PUMP_RELAY") (pin "86") (pinfunction "86_86") (pintype "passive"))
      (node (ref "RELAY_COIL_FUSE") (pin "1") (pinfunction "1A_1") (pintype "passive"))
      (node (ref "RUNNING_LIGHT") (pin "86") (pinfunction "86_86") (pintype "passive"))
      (node (ref "RUN_LIGHT_PWR") (pin "2A") (pinfunction "+_2A") (pintype "bidirectional"))
      (node (ref "R_HEADLIGHT") (pin "86") (pinfunction "86_86") (pintype "passive"))
      (node (ref "R_HEAD_PWR") (pin "2A") (pinfunction "+_2A") (pintype "bidirectional"))
      (node (ref "R_TAILLIGHT") (pin "86") (pinfunction "86_86") (pintype "passive"))
      (node (ref "R_TAIL_PWR") (pin "2A") (pinfunction "+_2A") (pintype "bidirectional"))
    )
    (net (code "2") (name "12_V") (class "Default")
      (node (ref "BRAKE_RELAY") (pin "87") (pinfunction "87_87") (pintype "passive"))
      (node (ref "CLUTCH_RELAY") (pin "87") (pinfunction "87_87") (pintype "passive"))
      (node (ref "CONTROL1") (pin "8") (pinfunction "8_8") (pintype "passive"))
      (node (ref "FAN_RELAY") (pin "87") (pinfunction "87_87") (pintype "passive"))
      (node (ref "HARNESS3/PWR") (pin "10") (pinfunction "10_10") (pintype "passive"))
      (node (ref "HARNESS3/PWR") (pin "11") (pinfunction "11_11") (pintype "passive"))
      (node (ref "HARNESS3/PWR") (pin "12") (pinfunction "12_12") (pintype "passive"))
      (node (ref "HARNESS3/PWR") (pin "6") (pinfunction "6_6") (pintype "passive"))
      (node (ref "HARNESS3/PWR") (pin "7") (pinfunction "7_7") (pintype "passive"))
      (node (ref "HARNESS3/PWR") (pin "8") (pinfunction "8_8") (pintype "passive"))
      (node (ref "HARNESS3/PWR") (pin "9") (pinfunction "9_9") (pintype "passive"))
      (node (ref "LA+_RELAY") (pin "87") (pinfunction "87_87") (pintype "passive"))
      (node (ref "LA-_RELAY") (pin "87") (pinfunction "87_87") (pintype "passive"))
      (node (ref "L_HEADLIGHT") (pin "87") (pinfunction "87_87") (pintype "passive"))
      (node (ref "L_TAILLIGHT") (pin "87") (pinfunction "87_87") (pintype "passive"))
      (node (ref "PUMP_RELAY") (pin "87") (pinfunction "87_87") (pintype "passive"))
      (node (ref "RELAY_COIL_FUSE") (pin "3") (pinfunction "2A_3") (pintype "passive"))
      (node (ref "RUNNING_LIGHT") (pin "87") (pinfunction "87_87") (pintype "passive"))
      (node (ref "R_HEADLIGHT") (pin "87") (pinfunction "87_87") (pintype "passive"))
      (node (ref "R_TAILLIGHT") (pin "87") (pinfunction "87_87") (pintype "passive"))
      (node (ref "SEAT_FUSE") (pin "1") (pinfunction "1A_1") (pintype "passive"))
    )
    (net (code "3") (name "ACC_IN") (class "Default")
      (node (ref "ACCESSORY_PWR_FUSE") (pin "1") (pinfunction "1A_1") (pintype "passive"))
      (node (ref "HARNESS2") (pin "11") (pinfunction "11_11") (pintype "passive"))
      (node (ref "HARNESS2") (pin "12") (pinfunction "12_12") (pintype "passive"))
    )
    (net (code "4") (name "ACC_OUT") (class "Default")
      (node (ref "ACCESSORY_PWR_FUSE") (pin "3") (pinfunction "2A_3") (pintype "passive"))
      (node (ref "HARNESS1") (pin "3") (pinfunction "3_3") (pintype "passive"))
      (node (ref "HARNESS1") (pin "4") (pinfunction "4_4") (pintype "passive"))
    )
    (net (code "5") (name "BRAKE") (class "Default")
      (node (ref "BRAKE_FUSE") (pin "1") (pinfunction "1A_1") (pintype "passive"))
      (node (ref "BRAKE_RELAY") (pin "30") (pinfunction "30_30") (pintype "passive"))
    )
    (net (code "6") (name "BRAKE_CTRL") (class "Default")
      (node (ref "BRAKE_RELAY") (pin "85") (pinfunction "85_85") (pintype "passive"))
      (node (ref "CONTROL2") (pin "4") (pinfunction "4_4") (pintype "passive"))
      (node (ref "D4") (pin "A") (pinfunction "A_A") (pintype "passive"))
      (node (ref "R9") (pin "2") (pinfunction "2_2") (pintype "passive"))
    )
    (net (code "7") (name "BRAKE_OUT") (class "Default")
      (node (ref "BRAKE_FUSE") (pin "3") (pinfunction "2A_3") (pintype "passive"))
      (node (ref "HARNESS1") (pin "11") (pinfunction "11_11") (pintype "passive"))
      (node (ref "HARNESS1") (pin "12") (pinfunction "12_12") (pintype "passive"))
    )
    (net (code "8") (name "CLUTCH") (class "Default")
      (node (ref "CLUTCH_FUSE") (pin "1") (pinfunction "1A_1") (pintype "passive"))
      (node (ref "CLUTCH_RELAY") (pin "30") (pinfunction "30_30") (pintype "passive"))
    )
    (net (code "9") (name "CLUTCH_CTRL") (class "Default")
      (node (ref "CLUTCH_RELAY") (pin "85") (pinfunction "85_85") (pintype "passive"))
      (node (ref "CONTROL2") (pin "3") (pinfunction "3_3") (pintype "passive"))
      (node (ref "D5") (pin "A") (pinfunction "A_A") (pintype "passive"))
      (node (ref "R8") (pin "2") (pinfunction "2_2") (pintype "passive"))
    )
    (net (code "10") (name "CLUTCH_OUT") (class "Default")
      (node (ref "CLUTCH_FUSE") (pin "3") (pinfunction "2A_3") (pintype "passive"))
      (node (ref "HARNESS1") (pin "5") (pinfunction "5_5") (pintype "passive"))
      (node (ref "HARNESS1") (pin "6") (pinfunction "6_6") (pintype "passive"))
    )
    (net (code "11") (name "DIG1_CTRL") (class "Default")
      (node (ref "CONTROL1") (pin "1") (pinfunction "1_1") (pintype "passive"))
      (node (ref "D14") (pin "A") (pinfunction "A_A") (pintype "passive"))
      (node (ref "DIGITAL_IN1") (pin "85") (pinfunction "85_85") (pintype "passive"))
      (node (ref "R3") (pin "2") (pinfunction "2_2") (pintype "passive"))
    )
    (net (code "12") (name "DIG2_CTRL") (class "Default")
      (node (ref "CONTROL1") (pin "2") (pinfunction "2_2") (pintype "passive"))
      (node (ref "D13") (pin "A") (pinfunction "A_A") (pintype "passive"))
      (node (ref "DIGITAL_IN2") (pin "85") (pinfunction "85_85") (pintype "passive"))
      (node (ref "R4") (pin "2") (pinfunction "2_2") (pintype "passive"))
    )
    (net (code "13") (name "DIG3_CTRL") (class "Default")
      (node (ref "CONTROL1") (pin "3") (pinfunction "3_3") (pintype "passive"))
      (node (ref "D12") (pin "A") (pinfunction "A_A") (pintype "passive"))
      (node (ref "DIGITAL_IN3") (pin "85") (pinfunction "85_85") (pintype "passive"))
      (node (ref "R5") (pin "2") (pinfunction "2_2") (pintype "passive"))
    )
    (net (code "14") (name "DIG4_CTRL") (class "Default")
      (node (ref "CONTROL1") (pin "4") (pinfunction "4_4") (pintype "passive"))
      (node (ref "D11") (pin "A") (pinfunction "A_A") (pintype "passive"))
      (node (ref "DIGITAL_IN4") (pin "85") (pinfunction "85_85") (pintype "passive"))
      (node (ref "R6") (pin "2") (pinfunction "2_2") (pintype "passive"))
    )
    (net (code "15") (name "DIG5_CTRL") (class "Default")
      (node (ref "CONTROL1") (pin "5") (pinfunction "5_5") (pintype "passive"))
      (node (ref "D10") (pin "A") (pinfunction "A_A") (pintype "passive"))
      (node (ref "DIGITAL_IN5") (pin "85") (pinfunction "85_85") (pintype "passive"))
      (node (ref "R2") (pin "2") (pinfunction "2_2") (pintype "passive"))
    )
    (net (code "16") (name "DIG6_CTRL") (class "Default")
      (node (ref "CONTROL1") (pin "6") (pinfunction "6_6") (pintype "passive"))
      (node (ref "D9") (pin "A") (pinfunction "A_A") (pintype "passive"))
      (node (ref "DIGITAL_IN6") (pin "85") (pinfunction "85_85") (pintype "passive"))
      (node (ref "R1") (pin "2") (pinfunction "2_2") (pintype "passive"))
    )
    (net (code "17") (name "DIG7_CTRL") (class "Default")
      (node (ref "CONTROL1") (pin "7") (pinfunction "7_7") (pintype "passive"))
      (node (ref "D8") (pin "A") (pinfunction "A_A") (pintype "passive"))
      (node (ref "DIGITAL_IN7") (pin "85") (pinfunction "85_85") (pintype "passive"))
      (node (ref "R19") (pin "2") (pinfunction "2_2") (pintype "passive"))
    )
    (net (code "18") (name "DIG_IN1") (class "Default")
      (node (ref "DIGITAL_IN1") (pin "30") (pinfunction "30_30") (pintype "passive"))
      (node (ref "SEVCON") (pin "1") (pinfunction "1_1") (pintype "passive"))
    )
    (net (code "19") (name "DIG_IN2") (class "Default")
      (node (ref "DIGITAL_IN2") (pin "30") (pinfunction "30_30") (pintype "passive"))
      (node (ref "SEVCON") (pin "2") (pinfunction "2_2") (pintype "passive"))
    )
    (net (code "20") (name "DIG_IN3") (class "Default")
      (node (ref "DIGITAL_IN3") (pin "30") (pinfunction "30_30") (pintype "passive"))
      (node (ref "SEVCON") (pin "3") (pinfunction "3_3") (pintype "passive"))
    )
    (net (code "21") (name "DIG_IN4") (class "Default")
      (node (ref "DIGITAL_IN4") (pin "30") (pinfunction "30_30") (pintype "passive"))
      (node (ref "SEVCON") (pin "4") (pinfunction "4_4") (pintype "passive"))
    )
    (net (code "22") (name "DIG_IN5") (class "Default")
      (node (ref "DIGITAL_IN5") (pin "30") (pinfunction "30_30") (pintype "passive"))
      (node (ref "SEVCON") (pin "5") (pinfunction "5_5") (pintype "passive"))
    )
    (net (code "23") (name "DIG_IN6") (class "Default")
      (node (ref "DIGITAL_IN6") (pin "30") (pinfunction "30_30") (pintype "passive"))
      (node (ref "SEVCON") (pin "6") (pinfunction "6_6") (pintype "passive"))
    )
    (net (code "24") (name "DIG_IN7") (class "Default")
      (node (ref "DIGITAL_IN7") (pin "30") (pinfunction "30_30") (pintype "passive"))
      (node (ref "SEVCON") (pin "7") (pinfunction "7_7") (pintype "passive"))
    )
    (net (code "25") (name "FANS") (class "Default")
      (node (ref "FAN_FUSE") (pin "1") (pinfunction "1A_1") (pintype "passive"))
      (node (ref "FAN_RELAY") (pin "30") (pinfunction "30_30") (pintype "passive"))
    )
    (net (code "26") (name "FANS_OUT") (class "Default")
      (node (ref "FAN_FUSE") (pin "3") (pinfunction "2A_3") (pintype "passive"))
      (node (ref "HARNESS2") (pin "1") (pinfunction "1_1") (pintype "passive"))
    )
    (net (code "27") (name "FAN_CTRL") (class "Default")
      (node (ref "CONTROL2") (pin "12") (pinfunction "12_12") (pintype "passive"))
      (node (ref "D6") (pin "A") (pinfunction "A_A") (pintype "passive"))
      (node (ref "FAN_RELAY") (pin "85") (pinfunction "85_85") (pintype "passive"))
      (node (ref "R7") (pin "2") (pinfunction "2_2") (pintype "passive"))
    )
    (net (code "28") (name "GND") (class "Default")
      (node (ref "DIGITAL_IN1") (pin "87") (pinfunction "87_87") (pintype "passive"))
      (node (ref "DIGITAL_IN2") (pin "87") (pinfunction "87_87") (pintype "passive"))
      (node (ref "DIGITAL_IN3") (pin "87") (pinfunction "87_87") (pintype "passive"))
      (node (ref "DIGITAL_IN4") (pin "87") (pinfunction "87_87") (pintype "passive"))
      (node (ref "DIGITAL_IN5") (pin "87") (pinfunction "87_87") (pintype "passive"))
      (node (ref "DIGITAL_IN6") (pin "87") (pinfunction "87_87") (pintype "passive"))
      (node (ref "DIGITAL_IN7") (pin "87") (pinfunction "87_87") (pintype "passive"))
      (node (ref "HARNESS3/PWR") (pin "3") (pinfunction "3_3") (pintype "passive"))
      (node (ref "HARNESS3/PWR") (pin "4") (pinfunction "4_4") (pintype "passive"))
      (node (ref "LA+_RELAY") (pin "87A") (pinfunction "87A_87A") (pintype "passive"))
      (node (ref "LA-_RELAY") (pin "87A") (pinfunction "87A_87A") (pintype "passive"))
    )
    (net (code "29") (name "INTERLOCK") (class "Default")
      (node (ref "INTERLOCK_FUSE") (pin "3") (pinfunction "2A_3") (pintype "passive"))
      (node (ref "INTERLOCK_RELAY") (pin "87") (pinfunction "87_87") (pintype "passive"))
    )
    (net (code "30") (name "INT_CTRL") (class "Default")
      (node (ref "CONTROL2") (pin "10") (pinfunction "10_10") (pintype "passive"))
      (node (ref "D1") (pin "A") (pinfunction "A_A") (pintype "passive"))
      (node (ref "INTERLOCK_RELAY") (pin "85") (pinfunction "85_85") (pintype "passive"))
      (node (ref "R12") (pin "1") (pinfunction "1_1") (pintype "passive"))
    )
    (net (code "31") (name "INT_IN") (class "Default")
      (node (ref "HARNESS3/PWR") (pin "1") (pinfunction "1_1") (pintype "passive"))
      (node (ref "HARNESS3/PWR") (pin "2") (pinfunction "2_2") (pintype "passive"))
      (node (ref "INTERLOCK_RELAY") (pin "30") (pinfunction "30_30") (pintype "passive"))
    )
    (net (code "32") (name "INT_OUT") (class "Default")
      (node (ref "HARNESS1") (pin "1") (pinfunction "1_1") (pintype "passive"))
      (node (ref "HARNESS1") (pin "2") (pinfunction "2_2") (pintype "passive"))
      (node (ref "INTERLOCK_FUSE") (pin "1") (pinfunction "1A_1") (pintype "passive"))
    )
    (net (code "33") (name "LA+") (class "Default")
      (node (ref "LA+_FUSE") (pin "1") (pinfunction "1A_1") (pintype "passive"))
      (node (ref "LA+_RELAY") (pin "30") (pinfunction "30_30") (pintype "passive"))
    )
    (net (code "34") (name "LA+_CTRL") (class "Default")
      (node (ref "CONTROL2") (pin "6") (pinfunction "6_6") (pintype "passive"))
      (node (ref "D2") (pin "A") (pinfunction "A_A") (pintype "passive"))
      (node (ref "LA+_RELAY") (pin "85") (pinfunction "85_85") (pintype "passive"))
      (node (ref "R11") (pin "2") (pinfunction "2_2") (pintype "passive"))
    )
    (net (code "35") (name "LA+_OUT") (class "Default")
      (node (ref "HARNESS1") (pin "7") (pinfunction "7_7") (pintype "passive"))
      (node (ref "HARNESS1") (pin "8") (pinfunction "8_8") (pintype "passive"))
      (node (ref "LA+_FUSE") (pin "3") (pinfunction "2A_3") (pintype "passive"))
    )
    (net (code "36") (name "LA-") (class "Default")
      (node (ref "LA-_FUSE") (pin "1") (pinfunction "1A_1") (pintype "passive"))
      (node (ref "LA-_RELAY") (pin "30") (pinfunction "30_30") (pintype "passive"))
    )
    (net (code "37") (name "LA-_CTRL") (class "Default")
      (node (ref "CONTROL2") (pin "7") (pinfunction "7_7") (pintype "passive"))
      (node (ref "D3") (pin "A") (pinfunction "A_A") (pintype "passive"))
      (node (ref "LA-_RELAY") (pin "85") (pinfunction "85_85") (pintype "passive"))
      (node (ref "R10") (pin "2") (pinfunction "2_2") (pintype "passive"))
    )
    (net (code "38") (name "LA-_OUT") (class "Default")
      (node (ref "HARNESS1") (pin "10") (pinfunction "10_10") (pintype "passive"))
      (node (ref "HARNESS1") (pin "9") (pinfunction "9_9") (pintype "passive"))
      (node (ref "LA-_FUSE") (pin "3") (pinfunction "2A_3") (pintype "passive"))
    )
    (net (code "39") (name "LHL_CTRL") (class "Default")
      (node (ref "CONTROL2") (pin "1") (pinfunction "1_1") (pintype "passive"))
      (node (ref "D16") (pin "A") (pinfunction "A_A") (pintype "passive"))
      (node (ref "L_HEADLIGHT") (pin "85") (pinfunction "85_85") (pintype "passive"))
      (node (ref "R14") (pin "2") (pinfunction "2_2") (pintype "passive"))
    )
    (net (code "40") (name "LHL_OUT") (class "Default")
      (node (ref "HARNESS2") (pin "4") (pinfunction "4_4") (pintype "passive"))
      (node (ref "L_HEADLIGHT_FUSE") (pin "3") (pinfunction "2A_3") (pintype "passive"))
    )
    (net (code "41") (name "LH_LIGHT") (class "Default")
      (node (ref "L_HEADLIGHT") (pin "30") (pinfunction "30_30") (pintype "passive"))
      (node (ref "L_HEADLIGHT_FUSE") (pin "1") (pinfunction "1A_1") (pintype "passive"))
    )
    (net (code "42") (name "LTL_CTRL") (class "Default")
      (node (ref "CONTROL2") (pin "9") (pinfunction "9_9") (pintype "passive"))
      (node (ref "D17") (pin "A") (pinfunction "A_A") (pintype "passive"))
      (node (ref "L_TAILLIGHT") (pin "85") (pinfunction "85_85") (pintype "passive"))
      (node (ref "R15") (pin "2") (pinfunction "2_2") (pintype "passive"))
    )
    (net (code "43") (name "LTL_OUT") (class "Default")
      (node (ref "HARNESS2") (pin "6") (pinfunction "6_6") (pintype "passive"))
      (node (ref "L_TAILLIGHT_FUSE") (pin "3") (pinfunction "2A_3") (pintype "passive"))
    )
    (net (code "44") (name "LT_LIGHT") (class "Default")
      (node (ref "L_TAILLIGHT") (pin "30") (pinfunction "30_30") (pintype "passive"))
      (node (ref "L_TAILLIGHT_FUSE") (pin "1") (pinfunction "1A_1") (pintype "passive"))
    )
    (net (code "45") (name "Net-(BRAKE_PWR--)") (class "Default")
      (node (ref "BRAKE_PWR") (pin "1A") (pinfunction "-_1A") (pintype "bidirectional"))
      (node (ref "R9") (pin "1") (pinfunction "1_1") (pintype "passive"))
    )
    (net (code "46") (name "Net-(CLUTCH_PWR--)") (class "Default")
      (node (ref "CLUTCH_PWR") (pin "1A") (pinfunction "-_1A") (pintype "bidirectional"))
      (node (ref "R8") (pin "1") (pinfunction "1_1") (pintype "passive"))
    )
    (net (code "47") (name "Net-(DIG1_GND--)") (class "Default")
      (node (ref "DIG1_GND") (pin "1A") (pinfunction "-_1A") (pintype "bidirectional"))
      (node (ref "R3") (pin "1") (pinfunction "1_1") (pintype "passive"))
    )
    (net (code "48") (name "Net-(DIG2_GND--)") (class "Default")
      (node (ref "DIG2_GND") (pin "1A") (pinfunction "-_1A") (pintype "bidirectional"))
      (node (ref "R4") (pin "1") (pinfunction "1_1") (pintype "passive"))
    )
    (net (code "49") (name "Net-(DIG3_GND--)") (class "Default")
      (node (ref "DIG3_GND") (pin "1A") (pinfunction "-_1A") (pintype "bidirectional"))
      (node (ref "R5") (pin "1") (pinfunction "1_1") (pintype "passive"))
    )
    (net (code "50") (name "Net-(DIG4_GND--)") (class "Default")
      (node (ref "DIG4_GND") (pin "1A") (pinfunction "-_1A") (pintype "bidirectional"))
      (node (ref "R6") (pin "1") (pinfunction "1_1") (pintype "passive"))
    )
    (net (code "51") (name "Net-(DIG5_GND--)") (class "Default")
      (node (ref "DIG5_GND") (pin "1A") (pinfunction "-_1A") (pintype "bidirectional"))
      (node (ref "R2") (pin "1") (pinfunction "1_1") (pintype "passive"))
    )
    (net (code "52") (name "Net-(DIG6_GND--)") (class "Default")
      (node (ref "DIG6_GND") (pin "1A") (pinfunction "-_1A") (pintype "bidirectional"))
      (node (ref "R1") (pin "1") (pinfunction "1_1") (pintype "passive"))
    )
    (net (code "53") (name "Net-(DIG7_GND--)") (class "Default")
      (node (ref "DIG7_GND") (pin "1A") (pinfunction "-_1A") (pintype "bidirectional"))
      (node (ref "R19") (pin "1") (pinfunction "1_1") (pintype "passive"))
    )
    (net (code "54") (name "Net-(FAN_PWR--)") (class "Default")
      (node (ref "FAN_PWR") (pin "1A") (pinfunction "-_1A") (pintype "bidirectional"))
      (node (ref "R7") (pin "1") (pinfunction "1_1") (pintype "passive"))
    )
    (net (code "55") (name "Net-(INTERLOCK_PWR--)") (class "Default")
      (node (ref "INTERLOCK_PWR") (pin "1A") (pinfunction "-_1A") (pintype "bidirectional"))
      (node (ref "R12") (pin "2") (pinfunction "2_2") (pintype "passive"))
    )
    (net (code "56") (name "Net-(LA+_PWR--)") (class "Default")
      (node (ref "LA+_PWR") (pin "1A") (pinfunction "-_1A") (pintype "bidirectional"))
      (node (ref "R11") (pin "1") (pinfunction "1_1") (pintype "passive"))
    )
    (net (code "57") (name "Net-(LA-_PWR--)") (class "Default")
      (node (ref "LA-_PWR") (pin "1A") (pinfunction "-_1A") (pintype "bidirectional"))
      (node (ref "R10") (pin "1") (pinfunction "1_1") (pintype "passive"))
    )
    (net (code "58") (name "Net-(L_HEAD_PWR--)") (class "Default")
      (node (ref "L_HEAD_PWR") (pin "1A") (pinfunction "-_1A") (pintype "bidirectional"))
      (node (ref "R14") (pin "1") (pinfunction "1_1") (pintype "passive"))
    )
    (net (code "59") (name "Net-(L_TAIL_PWR--)") (class "Default")
      (node (ref "L_TAIL_PWR") (pin "1A") (pinfunction "-_1A") (pintype "bidirectional"))
      (node (ref "R15") (pin "1") (pinfunction "1_1") (pintype "passive"))
    )
    (net (code "60") (name "Net-(PUMP_PWR--)") (class "Default")
      (node (ref "PUMP_PWR") (pin "1A") (pinfunction "-_1A") (pintype "bidirectional"))
      (node (ref "R13") (pin "1") (pinfunction "1_1") (pintype "passive"))
    )
    (net (code "61") (name "Net-(RUN_LIGHT_PWR--)") (class "Default")
      (node (ref "R18") (pin "1") (pinfunction "1_1") (pintype "passive"))
      (node (ref "RUN_LIGHT_PWR") (pin "1A") (pinfunction "-_1A") (pintype "bidirectional"))
    )
    (net (code "62") (name "Net-(R_HEAD_PWR--)") (class "Default")
      (node (ref "R17") (pin "1") (pinfunction "1_1") (pintype "passive"))
      (node (ref "R_HEAD_PWR") (pin "1A") (pinfunction "-_1A") (pintype "bidirectional"))
    )
    (net (code "63") (name "Net-(R_TAIL_PWR--)") (class "Default")
      (node (ref "R16") (pin "1") (pinfunction "1_1") (pintype "passive"))
      (node (ref "R_TAIL_PWR") (pin "1A") (pinfunction "-_1A") (pintype "bidirectional"))
    )
    (net (code "64") (name "PUMP") (class "Default")
      (node (ref "PUMP_FUSE") (pin "1") (pinfunction "1A_1") (pintype "passive"))
      (node (ref "PUMP_RELAY") (pin "30") (pinfunction "30_30") (pintype "passive"))
    )
    (net (code "65") (name "PUMP_CTRL") (class "Default")
      (node (ref "CONTROL2") (pin "5") (pinfunction "5_5") (pintype "passive"))
      (node (ref "D7") (pin "A") (pinfunction "A_A") (pintype "passive"))
      (node (ref "PUMP_RELAY") (pin "85") (pinfunction "85_85") (pintype "passive"))
      (node (ref "R13") (pin "2") (pinfunction "2_2") (pintype "passive"))
    )
    (net (code "66") (name "PUMP_OUT") (class "Default")
      (node (ref "HARNESS2") (pin "2") (pinfunction "2_2") (pintype "passive"))
      (node (ref "PUMP_FUSE") (pin "3") (pinfunction "2A_3") (pintype "passive"))
    )
    (net (code "67") (name "RHL_CTRL") (class "Default")
      (node (ref "CONTROL2") (pin "2") (pinfunction "2_2") (pintype "passive"))
      (node (ref "D19") (pin "A") (pinfunction "A_A") (pintype "passive"))
      (node (ref "R17") (pin "2") (pinfunction "2_2") (pintype "passive"))
      (node (ref "R_HEADLIGHT") (pin "85") (pinfunction "85_85") (pintype "passive"))
    )
    (net (code "68") (name "RHL_OUT") (class "Default")
      (node (ref "HARNESS2") (pin "3") (pinfunction "3_3") (pintype "passive"))
      (node (ref "R_HEADLIGHT_FUSE") (pin "3") (pinfunction "2A_3") (pintype "passive"))
    )
    (net (code "69") (name "RH_LIGHT") (class "Default")
      (node (ref "R_HEADLIGHT") (pin "30") (pinfunction "30_30") (pintype "passive"))
      (node (ref "R_HEADLIGHT_FUSE") (pin "1") (pinfunction "1A_1") (pintype "passive"))
    )
    (net (code "70") (name "RN_LIGHT") (class "Default")
      (node (ref "RUNNING_LIGHT") (pin "30") (pinfunction "30_30") (pintype "passive"))
      (node (ref "RUNNING_LIGHT_FUSE") (pin "1") (pinfunction "1A_1") (pintype "passive"))
    )
    (net (code "71") (name "RTL_CTRL") (class "Default")
      (node (ref "CONTROL2") (pin "11") (pinfunction "11_11") (pintype "passive"))
      (node (ref "D18") (pin "A") (pinfunction "A_A") (pintype "passive"))
      (node (ref "R16") (pin "2") (pinfunction "2_2") (pintype "passive"))
      (node (ref "R_TAILLIGHT") (pin "85") (pinfunction "85_85") (pintype "passive"))
    )
    (net (code "72") (name "RTL_OUT") (class "Default")
      (node (ref "HARNESS2") (pin "5") (pinfunction "5_5") (pintype "passive"))
      (node (ref "R_TAILLIGHT_FUSE") (pin "3") (pinfunction "2A_3") (pintype "passive"))
    )
    (net (code "73") (name "RT_LIGHT") (class "Default")
      (node (ref "R_TAILLIGHT") (pin "30") (pinfunction "30_30") (pintype "passive"))
      (node (ref "R_TAILLIGHT_FUSE") (pin "1") (pinfunction "1A_1") (pintype "passive"))
    )
    (net (code "74") (name "RUNL_CTRL") (class "Default")
      (node (ref "CONTROL2") (pin "8") (pinfunction "8_8") (pintype "passive"))
      (node (ref "D15") (pin "A") (pinfunction "A_A") (pintype "passive"))
      (node (ref "R18") (pin "2") (pinfunction "2_2") (pintype "passive"))
      (node (ref "RUNNING_LIGHT") (pin "85") (pinfunction "85_85") (pintype "passive"))
    )
    (net (code "75") (name "RUNL_OUT") (class "Default")
      (node (ref "HARNESS2") (pin "7") (pinfunction "7_7") (pintype "passive"))
      (node (ref "RUNNING_LIGHT_FUSE") (pin "3") (pinfunction "2A_3") (pintype "passive"))
    )
    (net (code "76") (name "SEAT_OUT") (class "Default")
      (node (ref "HARNESS2") (pin "10") (pinfunction "10_10") (pintype "passive"))
      (node (ref "HARNESS2") (pin "8") (pinfunction "8_8") (pintype "passive"))
      (node (ref "HARNESS2") (pin "9") (pinfunction "9_9") (pintype "passive"))
      (node (ref "SEAT_FUSE") (pin "3") (pinfunction "2A_3") (pintype "passive"))
    )
    (net (code "77") (name "unconnected-(ACCESSORY_PWR_FUSE-1B-Pad2)") (class "Default")
      (node (ref "ACCESSORY_PWR_FUSE") (pin "2") (pinfunction "1B_2") (pintype "passive"))
    )
    (net (code "78") (name "unconnected-(ACCESSORY_PWR_FUSE-2B-Pad4)") (class "Default")
      (node (ref "ACCESSORY_PWR_FUSE") (pin "4") (pinfunction "2B_4") (pintype "passive"))
    )
    (net (code "79") (name "unconnected-(BRAKE_FUSE-1B-Pad2)") (class "Default")
      (node (ref "BRAKE_FUSE") (pin "2") (pinfunction "1B_2") (pintype "passive"))
    )
    (net (code "80") (name "unconnected-(BRAKE_FUSE-2B-Pad4)") (class "Default")
      (node (ref "BRAKE_FUSE") (pin "4") (pinfunction "2B_4") (pintype "passive"))
    )
    (net (code "81") (name "unconnected-(BRAKE_RELAY-Pad87A)") (class "Default")
      (node (ref "BRAKE_RELAY") (pin "87A") (pinfunction "87A_87A") (pintype "passive"))
    )
    (net (code "82") (name "unconnected-(CLUTCH_FUSE-1B-Pad2)") (class "Default")
      (node (ref "CLUTCH_FUSE") (pin "2") (pinfunction "1B_2") (pintype "passive"))
    )
    (net (code "83") (name "unconnected-(CLUTCH_FUSE-2B-Pad4)") (class "Default")
      (node (ref "CLUTCH_FUSE") (pin "4") (pinfunction "2B_4") (pintype "passive"))
    )
    (net (code "84") (name "unconnected-(CLUTCH_RELAY-Pad87A)") (class "Default")
      (node (ref "CLUTCH_RELAY") (pin "87A") (pinfunction "87A_87A") (pintype "passive"))
    )
    (net (code "85") (name "unconnected-(CONTROL1-Pad9)") (class "Default")
      (node (ref "CONTROL1") (pin "9") (pinfunction "9_9") (pintype "passive"))
    )
    (net (code "86") (name "unconnected-(CONTROL1-Pad10)") (class "Default")
      (node (ref "CONTROL1") (pin "10") (pinfunction "10_10") (pintype "passive"))
    )
    (net (code "87") (name "unconnected-(CONTROL1-Pad11)") (class "Default")
      (node (ref "CONTROL1") (pin "11") (pinfunction "11_11") (pintype "passive"))
    )
    (net (code "88") (name "unconnected-(CONTROL1-Pad12)") (class "Default")
      (node (ref "CONTROL1") (pin "12") (pinfunction "12_12") (pintype "passive"))
    )
    (net (code "89") (name "unconnected-(DIGITAL_IN1-Pad87A)") (class "Default")
      (node (ref "DIGITAL_IN1") (pin "87A") (pinfunction "87A_87A") (pintype "passive"))
    )
    (net (code "90") (name "unconnected-(DIGITAL_IN2-Pad87A)") (class "Default")
      (node (ref "DIGITAL_IN2") (pin "87A") (pinfunction "87A_87A") (pintype "passive"))
    )
    (net (code "91") (name "unconnected-(DIGITAL_IN3-Pad87A)") (class "Default")
      (node (ref "DIGITAL_IN3") (pin "87A") (pinfunction "87A_87A") (pintype "passive"))
    )
    (net (code "92") (name "unconnected-(DIGITAL_IN4-Pad87A)") (class "Default")
      (node (ref "DIGITAL_IN4") (pin "87A") (pinfunction "87A_87A") (pintype "passive"))
    )
    (net (code "93") (name "unconnected-(DIGITAL_IN5-Pad87A)") (class "Default")
      (node (ref "DIGITAL_IN5") (pin "87A") (pinfunction "87A_87A") (pintype "passive"))
    )
    (net (code "94") (name "unconnected-(DIGITAL_IN6-Pad87A)") (class "Default")
      (node (ref "DIGITAL_IN6") (pin "87A") (pinfunction "87A_87A") (pintype "passive"))
    )
    (net (code "95") (name "unconnected-(DIGITAL_IN7-Pad87A)") (class "Default")
      (node (ref "DIGITAL_IN7") (pin "87A") (pinfunction "87A_87A") (pintype "passive"))
    )
    (net (code "96") (name "unconnected-(FAN_FUSE-1B-Pad2)") (class "Default")
      (node (ref "FAN_FUSE") (pin "2") (pinfunction "1B_2") (pintype "passive"))
    )
    (net (code "97") (name "unconnected-(FAN_FUSE-2B-Pad4)") (class "Default")
      (node (ref "FAN_FUSE") (pin "4") (pinfunction "2B_4") (pintype "passive"))
    )
    (net (code "98") (name "unconnected-(FAN_RELAY-Pad87A)") (class "Default")
      (node (ref "FAN_RELAY") (pin "87A") (pinfunction "87A_87A") (pintype "passive"))
    )
    (net (code "99") (name "unconnected-(HARNESS3/PWR-Pad5)") (class "Default")
      (node (ref "HARNESS3/PWR") (pin "5") (pinfunction "5_5") (pintype "passive"))
    )
    (net (code "100") (name "unconnected-(INTERLOCK_FUSE-1B-Pad2)") (class "Default")
      (node (ref "INTERLOCK_FUSE") (pin "2") (pinfunction "1B_2") (pintype "passive"))
    )
    (net (code "101") (name "unconnected-(INTERLOCK_FUSE-2B-Pad4)") (class "Default")
      (node (ref "INTERLOCK_FUSE") (pin "4") (pinfunction "2B_4") (pintype "passive"))
    )
    (net (code "102") (name "unconnected-(INTERLOCK_RELAY-Pad87A)") (class "Default")
      (node (ref "INTERLOCK_RELAY") (pin "87A") (pinfunction "87A_87A") (pintype "passive"))
    )
    (net (code "103") (name "unconnected-(LA+_FUSE-1B-Pad2)") (class "Default")
      (node (ref "LA+_FUSE") (pin "2") (pinfunction "1B_2") (pintype "passive"))
    )
    (net (code "104") (name "unconnected-(LA+_FUSE-2B-Pad4)") (class "Default")
      (node (ref "LA+_FUSE") (pin "4") (pinfunction "2B_4") (pintype "passive"))
    )
    (net (code "105") (name "unconnected-(LA-_FUSE-1B-Pad2)") (class "Default")
      (node (ref "LA-_FUSE") (pin "2") (pinfunction "1B_2") (pintype "passive"))
    )
    (net (code "106") (name "unconnected-(LA-_FUSE-2B-Pad4)") (class "Default")
      (node (ref "LA-_FUSE") (pin "4") (pinfunction "2B_4") (pintype "passive"))
    )
    (net (code "107") (name "unconnected-(L_HEADLIGHT-Pad87A)") (class "Default")
      (node (ref "L_HEADLIGHT") (pin "87A") (pinfunction "87A_87A") (pintype "passive"))
    )
    (net (code "108") (name "unconnected-(L_HEADLIGHT_FUSE-1B-Pad2)") (class "Default")
      (node (ref "L_HEADLIGHT_FUSE") (pin "2") (pinfunction "1B_2") (pintype "passive"))
    )
    (net (code "109") (name "unconnected-(L_HEADLIGHT_FUSE-2B-Pad4)") (class "Default")
      (node (ref "L_HEADLIGHT_FUSE") (pin "4") (pinfunction "2B_4") (pintype "passive"))
    )
    (net (code "110") (name "unconnected-(L_TAILLIGHT-Pad87A)") (class "Default")
      (node (ref "L_TAILLIGHT") (pin "87A") (pinfunction "87A_87A") (pintype "passive"))
    )
    (net (code "111") (name "unconnected-(L_TAILLIGHT_FUSE-1B-Pad2)") (class "Default")
      (node (ref "L_TAILLIGHT_FUSE") (pin "2") (pinfunction "1B_2") (pintype "passive"))
    )
    (net (code "112") (name "unconnected-(L_TAILLIGHT_FUSE-2B-Pad4)") (class "Default")
      (node (ref "L_TAILLIGHT_FUSE") (pin "4") (pinfunction "2B_4") (pintype "passive"))
    )
    (net (code "113") (name "unconnected-(PUMP_FUSE-1B-Pad2)") (class "Default")
      (node (ref "PUMP_FUSE") (pin "2") (pinfunction "1B_2") (pintype "passive"))
    )
    (net (code "114") (name "unconnected-(PUMP_FUSE-2B-Pad4)") (class "Default")
      (node (ref "PUMP_FUSE") (pin "4") (pinfunction "2B_4") (pintype "passive"))
    )
    (net (code "115") (name "unconnected-(PUMP_RELAY-Pad87A)") (class "Default")
      (node (ref "PUMP_RELAY") (pin "87A") (pinfunction "87A_87A") (pintype "passive"))
    )
    (net (code "116") (name "unconnected-(RELAY_COIL_FUSE-1B-Pad2)") (class "Default")
      (node (ref "RELAY_COIL_FUSE") (pin "2") (pinfunction "1B_2") (pintype "passive"))
    )
    (net (code "117") (name "unconnected-(RELAY_COIL_FUSE-2B-Pad4)") (class "Default")
      (node (ref "RELAY_COIL_FUSE") (pin "4") (pinfunction "2B_4") (pintype "passive"))
    )
    (net (code "118") (name "unconnected-(RUNNING_LIGHT-Pad87A)") (class "Default")
      (node (ref "RUNNING_LIGHT") (pin "87A") (pinfunction "87A_87A") (pintype "passive"))
    )
    (net (code "119") (name "unconnected-(RUNNING_LIGHT_FUSE-1B-Pad2)") (class "Default")
      (node (ref "RUNNING_LIGHT_FUSE") (pin "2") (pinfunction "1B_2") (pintype "passive"))
    )
    (net (code "120") (name "unconnected-(RUNNING_LIGHT_FUSE-2B-Pad4)") (class "Default")
      (node (ref "RUNNING_LIGHT_FUSE") (pin "4") (pinfunction "2B_4") (pintype "passive"))
    )
    (net (code "121") (name "unconnected-(R_HEADLIGHT-Pad87A)") (class "Default")
      (node (ref "R_HEADLIGHT") (pin "87A") (pinfunction "87A_87A") (pintype "passive"))
    )
    (net (code "122") (name "unconnected-(R_HEADLIGHT_FUSE-1B-Pad2)") (class "Default")
      (node (ref "R_HEADLIGHT_FUSE") (pin "2") (pinfunction "1B_2") (pintype "passive"))
    )
    (net (code "123") (name "unconnected-(R_HEADLIGHT_FUSE-2B-Pad4)") (class "Default")
      (node (ref "R_HEADLIGHT_FUSE") (pin "4") (pinfunction "2B_4") (pintype "passive"))
    )
    (net (code "124") (name "unconnected-(R_TAILLIGHT-Pad87A)") (class "Default")
      (node (ref "R_TAILLIGHT") (pin "87A") (pinfunction "87A_87A") (pintype "passive"))
    )
    (net (code "125") (name "unconnected-(R_TAILLIGHT_FUSE-1B-Pad2)") (class "Default")
      (node (ref "R_TAILLIGHT_FUSE") (pin "2") (pinfunction "1B_2") (pintype "passive"))
    )
    (net (code "126") (name "unconnected-(R_TAILLIGHT_FUSE-2B-Pad4)") (class "Default")
      (node (ref "R_TAILLIGHT_FUSE") (pin "4") (pinfunction "2B_4") (pintype "passive"))
    )
    (net (code "127") (name "unconnected-(SEAT_FUSE-1B-Pad2)") (class "Default")
      (node (ref "SEAT_FUSE") (pin "2") (pinfunction "1B_2") (pintype "passive"))
    )
    (net (code "128") (name "unconnected-(SEAT_FUSE-2B-Pad4)") (class "Default")
      (node (ref "SEAT_FUSE") (pin "4") (pinfunction "2B_4") (pintype "passive"))
    )
    (net (code "129") (name "unconnected-(SEVCON-Pad8)") (class "Default")
      (node (ref "SEVCON") (pin "8") (pinfunction "8_8") (pintype "passive"))
    )
    (net (code "130") (name "unconnected-(SEVCON-Pad9)") (class "Default")
      (node (ref "SEVCON") (pin "9") (pinfunction "9_9") (pintype "passive"))
    )
    (net (code "131") (name "unconnected-(SEVCON-Pad10)") (class "Default")
      (node (ref "SEVCON") (pin "10") (pinfunction "10_10") (pintype "passive"))
    )
    (net (code "132") (name "unconnected-(SEVCON-Pad11)") (class "Default")
      (node (ref "SEVCON") (pin "11") (pinfunction "11_11") (pintype "passive"))
    )
    (net (code "133") (name "unconnected-(SEVCON-Pad12)") (class "Default")
      (node (ref "SEVCON") (pin "12") (pinfunction "12_12") (pintype "passive"))
    )
  )
)
